# 01_fpga.net
KiCad netlist of a schematic drawn in Altium Designer
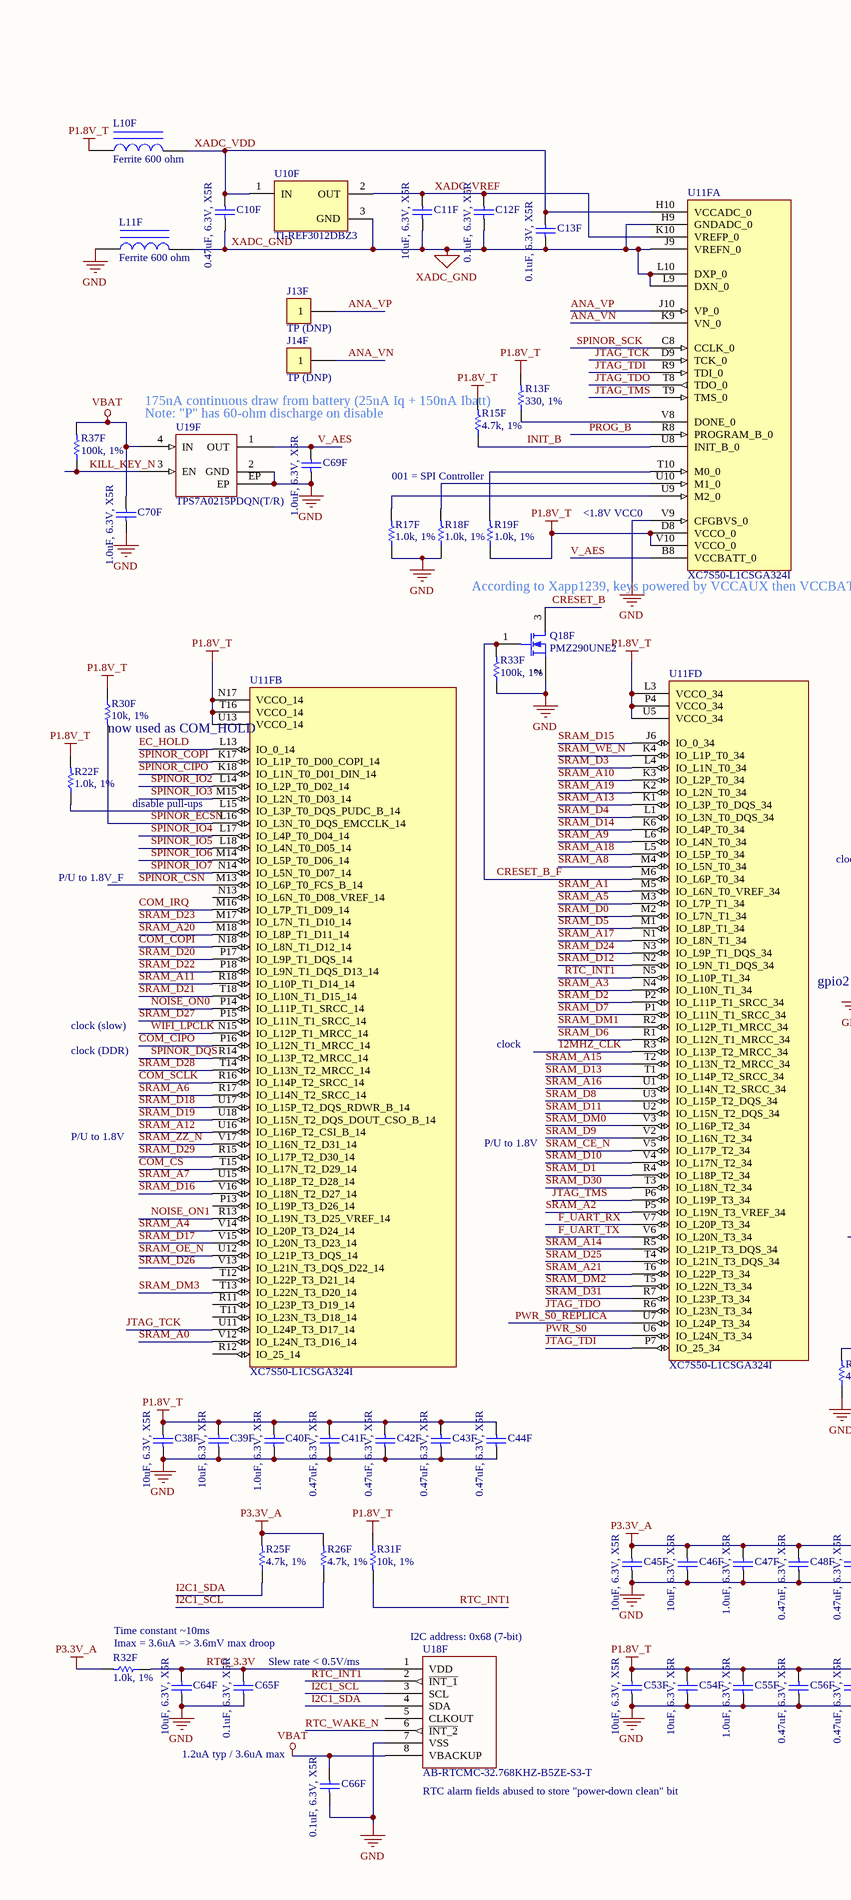
[diagram p0: 01_fpga.SchDoc, left]
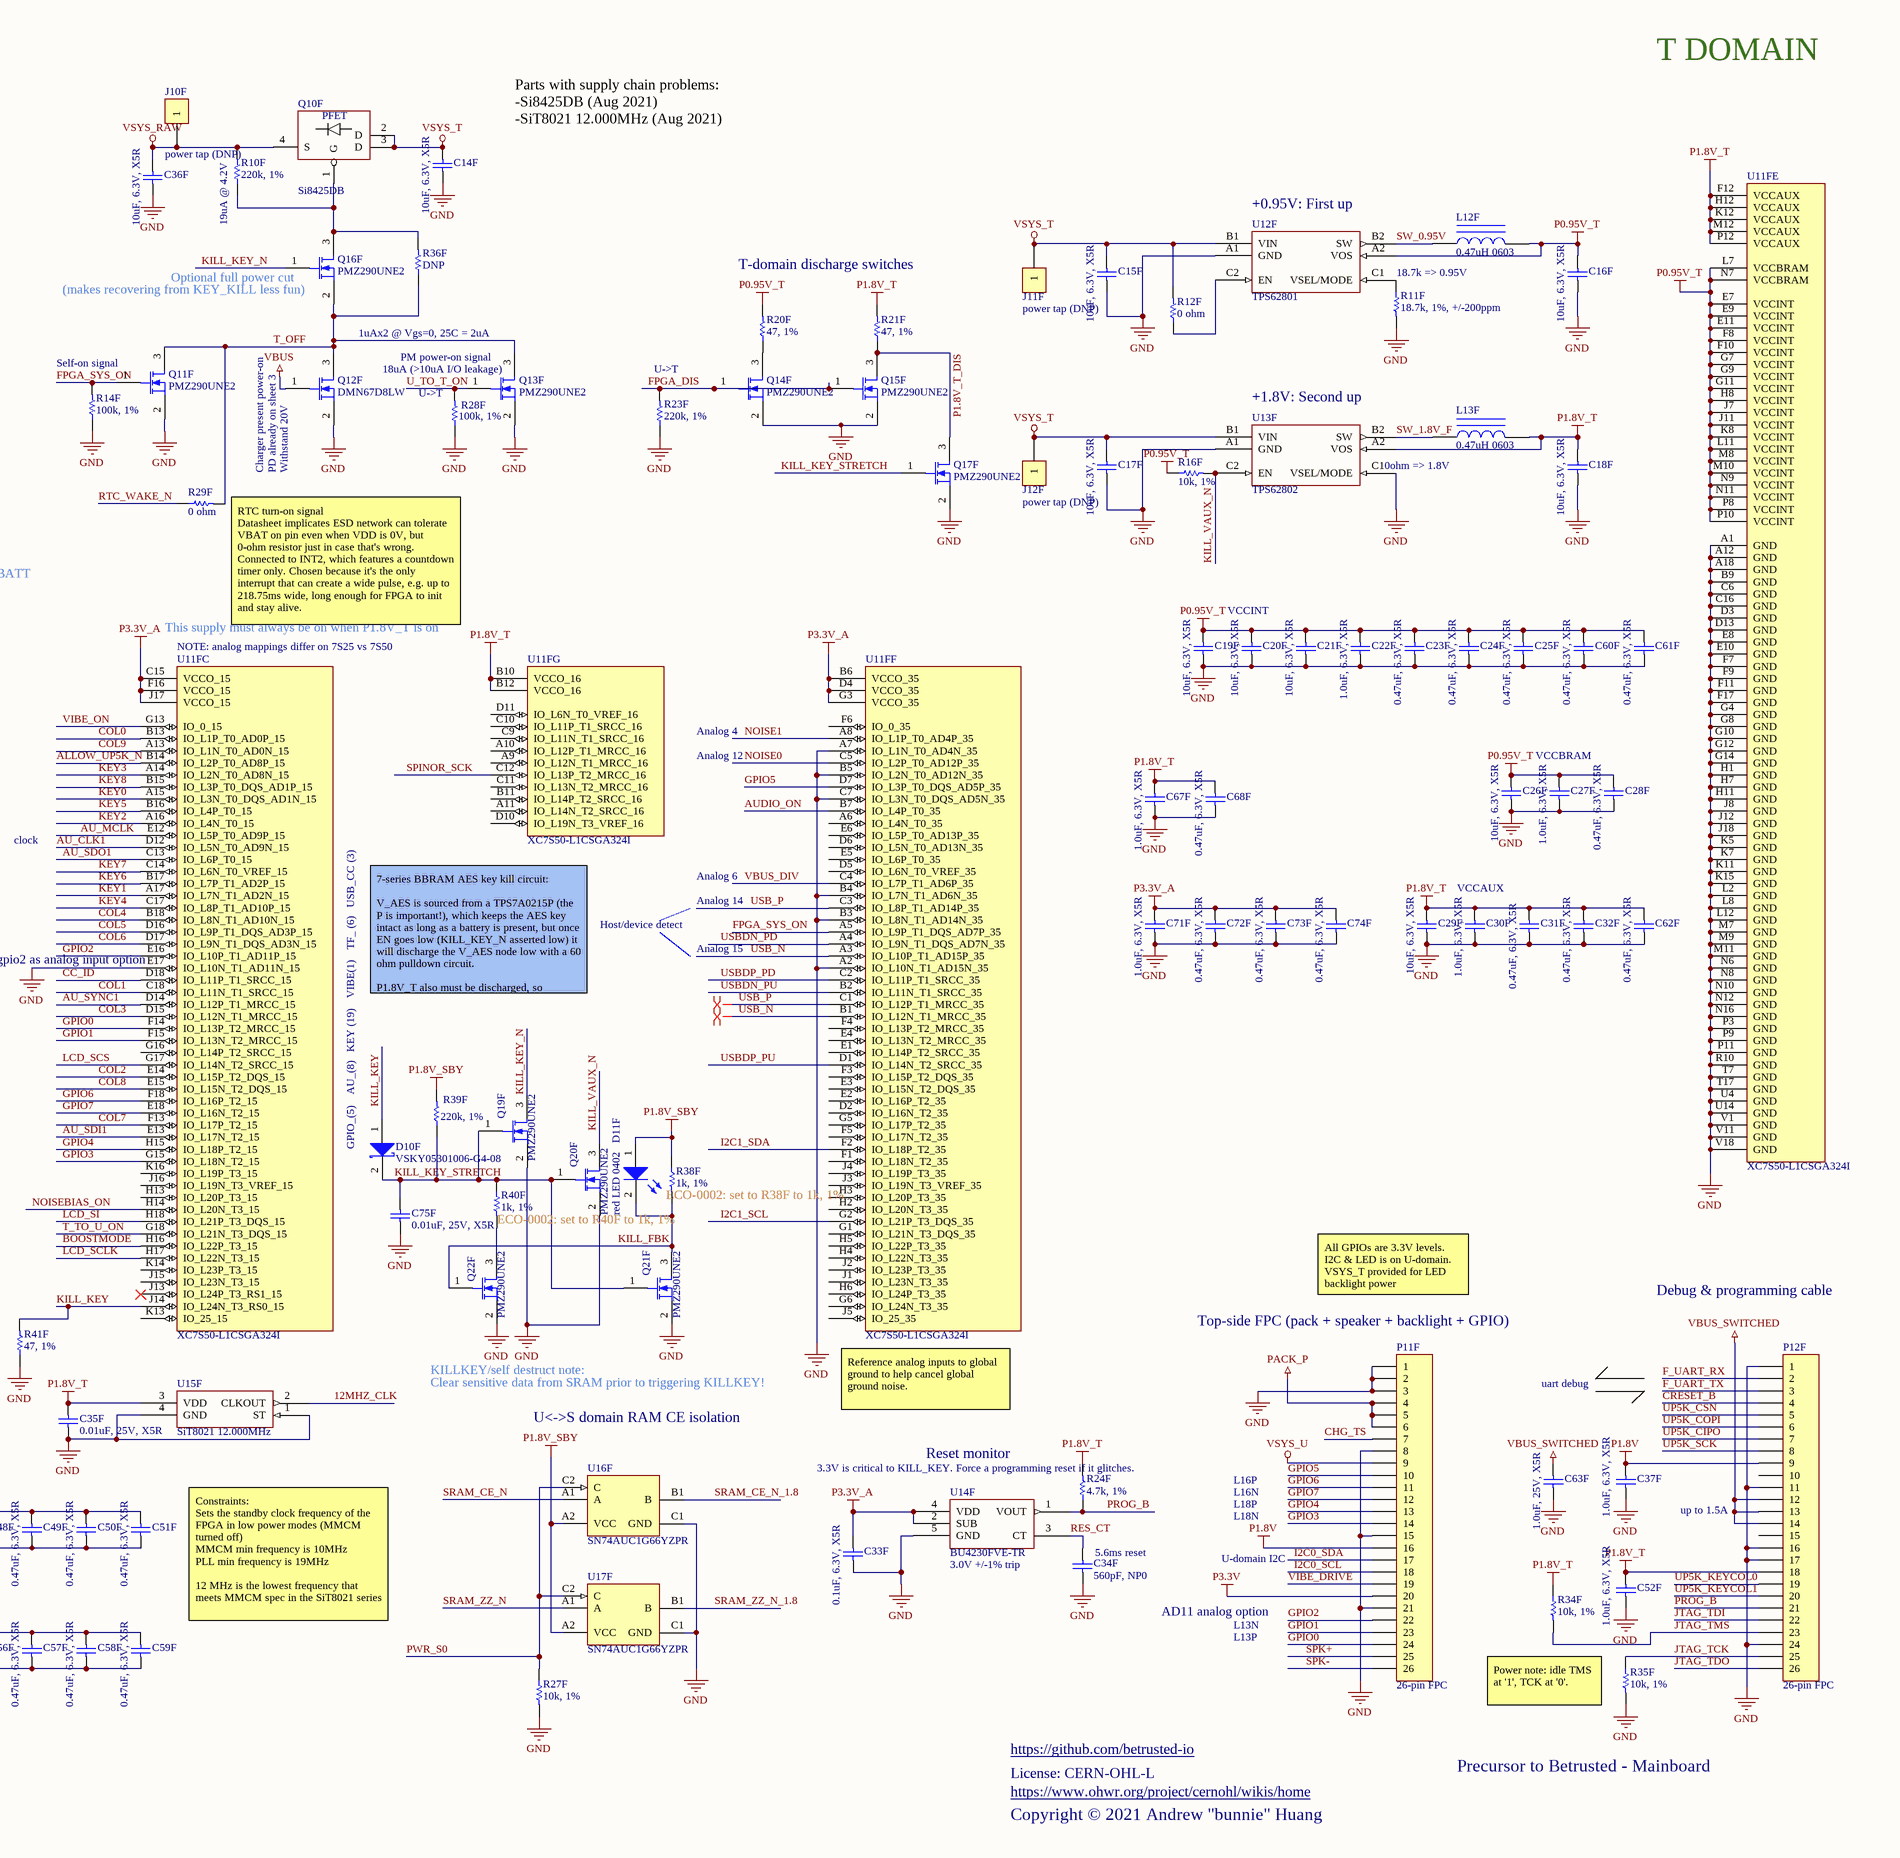
[diagram p1: 01_fpga.SchDoc, right]

(export (version "E")
  (design (tool "Eeschema 10.0.6"))
  (components
    (comp (ref "C10F")
      (value "0.47uF, 6.3V, X5R")
      (footprint "B_CAP0201")
      (description "Capacitor (Semiconductor SIM Model)")
      (fields (field (name "MPN") "CL03A474KQ3NNNH"))
      (libsource (lib "Miscellaneous Devices") (part "Cap Semi"))
    )
    (comp (ref "C11F")
      (value "10uF, 6.3V, X5R")
      (footprint "B_CAP0603")
      (description "Capacitor (Semiconductor SIM Model)")
      (fields (field (name "MPN") "CL10A106MQ8NNNC"))
      (libsource (lib "Miscellaneous Devices") (part "Cap Semi"))
    )
    (comp (ref "C12F")
      (value "0.1uF, 6.3V, X5R")
      (footprint "B_CAP0201")
      (description "Capacitor (Semiconductor SIM Model)")
      (fields (field (name "MPN") "CL03A104KQ3NNNC"))
      (libsource (lib "Miscellaneous Devices") (part "Cap Semi"))
    )
    (comp (ref "C13F")
      (value "0.1uF, 6.3V, X5R")
      (footprint "B_CAP0201")
      (description "Capacitor (Semiconductor SIM Model)")
      (fields (field (name "MPN") "CL03A104KQ3NNNC"))
      (libsource (lib "Miscellaneous Devices") (part "Cap Semi"))
    )
    (comp (ref "C14F")
      (value "10uF, 6.3V, X5R")
      (footprint "B_CAP0603")
      (description "Capacitor (Semiconductor SIM Model)")
      (fields (field (name "MPN") "CL10A106MQ8NNNC"))
      (libsource (lib "Miscellaneous Devices") (part "Cap Semi"))
    )
    (comp (ref "C15F")
      (value "10uF, 6.3V, X5R")
      (footprint "B_CAP0603")
      (description "Capacitor (Semiconductor SIM Model)")
      (fields (field (name "MPN") "CL10A106MQ8NNNC"))
      (libsource (lib "Miscellaneous Devices") (part "Cap Semi"))
    )
    (comp (ref "C16F")
      (value "10uF, 6.3V, X5R")
      (footprint "B_CAP0603")
      (description "Capacitor (Semiconductor SIM Model)")
      (fields (field (name "MPN") "CL10A106MQ8NNNC"))
      (libsource (lib "Miscellaneous Devices") (part "Cap Semi"))
    )
    (comp (ref "C17F")
      (value "10uF, 6.3V, X5R")
      (footprint "B_CAP0603")
      (description "Capacitor (Semiconductor SIM Model)")
      (fields (field (name "MPN") "CL10A106MQ8NNNC"))
      (libsource (lib "Miscellaneous Devices") (part "Cap Semi"))
    )
    (comp (ref "C18F")
      (value "10uF, 6.3V, X5R")
      (footprint "B_CAP0603")
      (description "Capacitor (Semiconductor SIM Model)")
      (fields (field (name "MPN") "CL10A106MQ8NNNC"))
      (libsource (lib "Miscellaneous Devices") (part "Cap Semi"))
    )
    (comp (ref "C19F")
      (value "10uF, 6.3V, X5R")
      (footprint "B_CAP0603")
      (description "Capacitor (Semiconductor SIM Model)")
      (fields (field (name "MPN") "CL10A106MQ8NNNC"))
      (libsource (lib "Miscellaneous Devices") (part "Cap Semi"))
    )
    (comp (ref "C20F")
      (value "10uF, 6.3V, X5R")
      (footprint "B_CAP0603")
      (description "Capacitor (Semiconductor SIM Model)")
      (fields (field (name "MPN") "CL10A106MQ8NNNC"))
      (libsource (lib "Miscellaneous Devices") (part "Cap Semi"))
    )
    (comp (ref "C21F")
      (value "10uF, 6.3V, X5R")
      (footprint "B_CAP0603")
      (description "Capacitor (Semiconductor SIM Model)")
      (fields (field (name "MPN") "CL10A106MQ8NNNC"))
      (libsource (lib "Miscellaneous Devices") (part "Cap Semi"))
    )
    (comp (ref "C22F")
      (value "1.0uF, 6.3V, X5R")
      (footprint "B_CAP0201")
      (description "Capacitor (Semiconductor SIM Model)")
      (fields (field (name "MPN") "GRM033R60J105MEA2D"))
      (libsource (lib "Miscellaneous Devices") (part "Cap Semi"))
    )
    (comp (ref "C23F")
      (value "0.47uF, 6.3V, X5R")
      (footprint "B_CAP0201")
      (description "Capacitor (Semiconductor SIM Model)")
      (fields (field (name "MPN") "CL03A474KQ3NNNH"))
      (libsource (lib "Miscellaneous Devices") (part "Cap Semi"))
    )
    (comp (ref "C24F")
      (value "0.47uF, 6.3V, X5R")
      (footprint "B_CAP0201")
      (description "Capacitor (Semiconductor SIM Model)")
      (fields (field (name "MPN") "CL03A474KQ3NNNH"))
      (libsource (lib "Miscellaneous Devices") (part "Cap Semi"))
    )
    (comp (ref "C25F")
      (value "0.47uF, 6.3V, X5R")
      (footprint "B_CAP0201")
      (description "Capacitor (Semiconductor SIM Model)")
      (fields (field (name "MPN") "CL03A474KQ3NNNH"))
      (libsource (lib "Miscellaneous Devices") (part "Cap Semi"))
    )
    (comp (ref "C26F")
      (value "10uF, 6.3V, X5R")
      (footprint "B_CAP0603")
      (description "Capacitor (Semiconductor SIM Model)")
      (fields (field (name "MPN") "CL10A106MQ8NNNC"))
      (libsource (lib "Miscellaneous Devices") (part "Cap Semi"))
    )
    (comp (ref "C27F")
      (value "1.0uF, 6.3V, X5R")
      (footprint "B_CAP0201")
      (description "Capacitor (Semiconductor SIM Model)")
      (fields (field (name "MPN") "GRM033R60J105MEA2D"))
      (libsource (lib "Miscellaneous Devices") (part "Cap Semi"))
    )
    (comp (ref "C28F")
      (value "0.47uF, 6.3V, X5R")
      (footprint "B_CAP0201")
      (description "Capacitor (Semiconductor SIM Model)")
      (fields (field (name "MPN") "CL03A474KQ3NNNH"))
      (libsource (lib "Miscellaneous Devices") (part "Cap Semi"))
    )
    (comp (ref "C29F")
      (value "10uF, 6.3V, X5R")
      (footprint "B_CAP0603")
      (description "Capacitor (Semiconductor SIM Model)")
      (fields (field (name "MPN") "CL10A106MQ8NNNC"))
      (libsource (lib "Miscellaneous Devices") (part "Cap Semi"))
    )
    (comp (ref "C30F")
      (value "1.0uF, 6.3V, X5R")
      (footprint "B_CAP0201")
      (description "Capacitor (Semiconductor SIM Model)")
      (fields (field (name "MPN") "GRM033R60J105MEA2D"))
      (libsource (lib "Miscellaneous Devices") (part "Cap Semi"))
    )
    (comp (ref "C31F")
      (value "0.47uF, 6.3V, X5R")
      (footprint "B_CAP0201")
      (description "Capacitor (Semiconductor SIM Model)")
      (fields (field (name "MPN") "CL03A474KQ3NNNH"))
      (libsource (lib "Miscellaneous Devices") (part "Cap Semi"))
    )
    (comp (ref "C32F")
      (value "0.47uF, 6.3V, X5R")
      (footprint "B_CAP0201")
      (description "Capacitor (Semiconductor SIM Model)")
      (fields (field (name "MPN") "CL03A474KQ3NNNH"))
      (libsource (lib "Miscellaneous Devices") (part "Cap Semi"))
    )
    (comp (ref "C33F")
      (value "0.1uF, 6.3V, X5R")
      (footprint "B_CAP0201")
      (description "Capacitor (Semiconductor SIM Model)")
      (fields (field (name "MPN") "CL03A104KQ3NNNC"))
      (libsource (lib "Miscellaneous Devices") (part "Cap Semi"))
    )
    (comp (ref "C34F")
      (value "560pF, NP0")
      (footprint "B_RES0201")
      (description "Capacitor (Semiconductor SIM Model)")
      (fields (field (name "MPN") "GRM0335C1E561JA01D"))
      (libsource (lib "Miscellaneous Devices") (part "Cap Semi"))
    )
    (comp (ref "C35F")
      (value "0.01uF, 25V, X5R")
      (footprint "B_RES0201")
      (description "Capacitor (Semiconductor SIM Model)")
      (fields (field (name "MPN") "GRM033R61E103KA12D"))
      (libsource (lib "Miscellaneous Devices") (part "Cap Semi"))
    )
    (comp (ref "C36F")
      (value "10uF, 6.3V, X5R")
      (footprint "B_CAP0603")
      (description "Capacitor (Semiconductor SIM Model)")
      (fields (field (name "MPN") "CL10A106MQ8NNNC"))
      (libsource (lib "Miscellaneous Devices") (part "Cap Semi"))
    )
    (comp (ref "C37F")
      (value "1.0uF, 6.3V, X5R")
      (footprint "B_CAP0201")
      (description "Capacitor (Semiconductor SIM Model)")
      (fields (field (name "MPN") "GRM033R60J105MEA2D"))
      (libsource (lib "Miscellaneous Devices") (part "Cap Semi"))
    )
    (comp (ref "C38F")
      (value "10uF, 6.3V, X5R")
      (footprint "B_CAP0603")
      (description "Capacitor (Semiconductor SIM Model)")
      (fields (field (name "MPN") "CL10A106MQ8NNNC"))
      (libsource (lib "Miscellaneous Devices") (part "Cap Semi"))
    )
    (comp (ref "C39F")
      (value "10uF, 6.3V, X5R")
      (footprint "B_CAP0603")
      (description "Capacitor (Semiconductor SIM Model)")
      (fields (field (name "MPN") "CL10A106MQ8NNNC"))
      (libsource (lib "Miscellaneous Devices") (part "Cap Semi"))
    )
    (comp (ref "C40F")
      (value "1.0uF, 6.3V, X5R")
      (footprint "B_CAP0201")
      (description "Capacitor (Semiconductor SIM Model)")
      (fields (field (name "MPN") "GRM033R60J105MEA2D"))
      (libsource (lib "Miscellaneous Devices") (part "Cap Semi"))
    )
    (comp (ref "C41F")
      (value "0.47uF, 6.3V, X5R")
      (footprint "B_CAP0201")
      (description "Capacitor (Semiconductor SIM Model)")
      (fields (field (name "MPN") "CL03A474KQ3NNNH"))
      (libsource (lib "Miscellaneous Devices") (part "Cap Semi"))
    )
    (comp (ref "C42F")
      (value "0.47uF, 6.3V, X5R")
      (footprint "B_CAP0201")
      (description "Capacitor (Semiconductor SIM Model)")
      (fields (field (name "MPN") "CL03A474KQ3NNNH"))
      (libsource (lib "Miscellaneous Devices") (part "Cap Semi"))
    )
    (comp (ref "C43F")
      (value "0.47uF, 6.3V, X5R")
      (footprint "B_CAP0201")
      (description "Capacitor (Semiconductor SIM Model)")
      (fields (field (name "MPN") "CL03A474KQ3NNNH"))
      (libsource (lib "Miscellaneous Devices") (part "Cap Semi"))
    )
    (comp (ref "C44F")
      (value "0.47uF, 6.3V, X5R")
      (footprint "B_CAP0201")
      (description "Capacitor (Semiconductor SIM Model)")
      (fields (field (name "MPN") "CL03A474KQ3NNNH"))
      (libsource (lib "Miscellaneous Devices") (part "Cap Semi"))
    )
    (comp (ref "C45F")
      (value "10uF, 6.3V, X5R")
      (footprint "B_CAP0603")
      (description "Capacitor (Semiconductor SIM Model)")
      (fields (field (name "MPN") "CL10A106MQ8NNNC"))
      (libsource (lib "Miscellaneous Devices") (part "Cap Semi"))
    )
    (comp (ref "C46F")
      (value "10uF, 6.3V, X5R")
      (footprint "B_CAP0603")
      (description "Capacitor (Semiconductor SIM Model)")
      (fields (field (name "MPN") "CL10A106MQ8NNNC"))
      (libsource (lib "Miscellaneous Devices") (part "Cap Semi"))
    )
    (comp (ref "C47F")
      (value "1.0uF, 6.3V, X5R")
      (footprint "B_CAP0201")
      (description "Capacitor (Semiconductor SIM Model)")
      (fields (field (name "MPN") "GRM033R60J105MEA2D"))
      (libsource (lib "Miscellaneous Devices") (part "Cap Semi"))
    )
    (comp (ref "C48F")
      (value "0.47uF, 6.3V, X5R")
      (footprint "B_CAP0201")
      (description "Capacitor (Semiconductor SIM Model)")
      (fields (field (name "MPN") "CL03A474KQ3NNNH"))
      (libsource (lib "Miscellaneous Devices") (part "Cap Semi"))
    )
    (comp (ref "C49F")
      (value "0.47uF, 6.3V, X5R")
      (footprint "B_CAP0201")
      (description "Capacitor (Semiconductor SIM Model)")
      (fields (field (name "MPN") "CL03A474KQ3NNNH"))
      (libsource (lib "Miscellaneous Devices") (part "Cap Semi"))
    )
    (comp (ref "C50F")
      (value "0.47uF, 6.3V, X5R")
      (footprint "B_CAP0201")
      (description "Capacitor (Semiconductor SIM Model)")
      (fields (field (name "MPN") "CL03A474KQ3NNNH"))
      (libsource (lib "Miscellaneous Devices") (part "Cap Semi"))
    )
    (comp (ref "C51F")
      (value "0.47uF, 6.3V, X5R")
      (footprint "B_CAP0201")
      (description "Capacitor (Semiconductor SIM Model)")
      (fields (field (name "MPN") "CL03A474KQ3NNNH"))
      (libsource (lib "Miscellaneous Devices") (part "Cap Semi"))
    )
    (comp (ref "C52F")
      (value "1.0uF, 6.3V, X5R")
      (footprint "B_CAP0201")
      (description "Capacitor (Semiconductor SIM Model)")
      (fields (field (name "MPN") "GRM033R60J105MEA2D"))
      (libsource (lib "Miscellaneous Devices") (part "Cap Semi"))
    )
    (comp (ref "C53F")
      (value "10uF, 6.3V, X5R")
      (footprint "B_CAP0603")
      (description "Capacitor (Semiconductor SIM Model)")
      (fields (field (name "MPN") "CL10A106MQ8NNNC"))
      (libsource (lib "Miscellaneous Devices") (part "Cap Semi"))
    )
    (comp (ref "C54F")
      (value "10uF, 6.3V, X5R")
      (footprint "B_CAP0603")
      (description "Capacitor (Semiconductor SIM Model)")
      (fields (field (name "MPN") "CL10A106MQ8NNNC"))
      (libsource (lib "Miscellaneous Devices") (part "Cap Semi"))
    )
    (comp (ref "C55F")
      (value "1.0uF, 6.3V, X5R")
      (footprint "B_CAP0201")
      (description "Capacitor (Semiconductor SIM Model)")
      (fields (field (name "MPN") "GRM033R60J105MEA2D"))
      (libsource (lib "Miscellaneous Devices") (part "Cap Semi"))
    )
    (comp (ref "C56F")
      (value "0.47uF, 6.3V, X5R")
      (footprint "B_CAP0201")
      (description "Capacitor (Semiconductor SIM Model)")
      (fields (field (name "MPN") "CL03A474KQ3NNNH"))
      (libsource (lib "Miscellaneous Devices") (part "Cap Semi"))
    )
    (comp (ref "C57F")
      (value "0.47uF, 6.3V, X5R")
      (footprint "B_CAP0201")
      (description "Capacitor (Semiconductor SIM Model)")
      (fields (field (name "MPN") "CL03A474KQ3NNNH"))
      (libsource (lib "Miscellaneous Devices") (part "Cap Semi"))
    )
    (comp (ref "C58F")
      (value "0.47uF, 6.3V, X5R")
      (footprint "B_CAP0201")
      (description "Capacitor (Semiconductor SIM Model)")
      (fields (field (name "MPN") "CL03A474KQ3NNNH"))
      (libsource (lib "Miscellaneous Devices") (part "Cap Semi"))
    )
    (comp (ref "C59F")
      (value "0.47uF, 6.3V, X5R")
      (footprint "B_CAP0201")
      (description "Capacitor (Semiconductor SIM Model)")
      (fields (field (name "MPN") "CL03A474KQ3NNNH"))
      (libsource (lib "Miscellaneous Devices") (part "Cap Semi"))
    )
    (comp (ref "C60F")
      (value "0.47uF, 6.3V, X5R")
      (footprint "B_CAP0201")
      (description "Capacitor (Semiconductor SIM Model)")
      (fields (field (name "MPN") "CL03A474KQ3NNNH"))
      (libsource (lib "Miscellaneous Devices") (part "Cap Semi"))
    )
    (comp (ref "C61F")
      (value "0.47uF, 6.3V, X5R")
      (footprint "B_CAP0201")
      (description "Capacitor (Semiconductor SIM Model)")
      (fields (field (name "MPN") "CL03A474KQ3NNNH"))
      (libsource (lib "Miscellaneous Devices") (part "Cap Semi"))
    )
    (comp (ref "C62F")
      (value "0.47uF, 6.3V, X5R")
      (footprint "B_CAP0201")
      (description "Capacitor (Semiconductor SIM Model)")
      (fields (field (name "MPN") "CL03A474KQ3NNNH"))
      (libsource (lib "Miscellaneous Devices") (part "Cap Semi"))
    )
    (comp (ref "C63F")
      (value "1.0uF, 25V, X5R")
      (footprint "B_CAP0603")
      (description "Capacitor (Semiconductor SIM Model)")
      (fields (field (name "MPN") "CL10A105KA8NNNC"))
      (libsource (lib "Miscellaneous Devices") (part "Cap Semi"))
    )
    (comp (ref "C64F")
      (value "10uF, 6.3V, X5R")
      (footprint "B_CAP0603")
      (description "Capacitor (Semiconductor SIM Model)")
      (fields (field (name "MPN") "CL10A106MQ8NNNC"))
      (libsource (lib "Miscellaneous Devices") (part "Cap Semi"))
    )
    (comp (ref "C65F")
      (value "0.1uF, 6.3V, X5R")
      (footprint "B_CAP0201")
      (description "Capacitor (Semiconductor SIM Model)")
      (fields (field (name "MPN") "CL03A104KQ3NNNC"))
      (libsource (lib "Miscellaneous Devices") (part "Cap Semi"))
    )
    (comp (ref "C66F")
      (value "0.1uF, 6.3V, X5R")
      (footprint "B_CAP0201")
      (description "Capacitor (Semiconductor SIM Model)")
      (fields (field (name "MPN") "CL03A104KQ3NNNC"))
      (libsource (lib "Miscellaneous Devices") (part "Cap Semi"))
    )
    (comp (ref "C67F")
      (value "1.0uF, 6.3V, X5R")
      (footprint "B_CAP0201")
      (description "Capacitor (Semiconductor SIM Model)")
      (fields (field (name "MPN") "GRM033R60J105MEA2D"))
      (libsource (lib "Miscellaneous Devices") (part "Cap Semi"))
    )
    (comp (ref "C68F")
      (value "0.47uF, 6.3V, X5R")
      (footprint "B_CAP0201")
      (description "Capacitor (Semiconductor SIM Model)")
      (fields (field (name "MPN") "CL03A474KQ3NNNH"))
      (libsource (lib "Miscellaneous Devices") (part "Cap Semi"))
    )
    (comp (ref "C69F")
      (value "1.0uF, 6.3V, X5R")
      (footprint "B_CAP0201")
      (description "Capacitor (Semiconductor SIM Model)")
      (fields (field (name "MPN") "GRM033R60J105MEA2D"))
      (libsource (lib "Miscellaneous Devices") (part "Cap Semi"))
    )
    (comp (ref "C70F")
      (value "1.0uF, 6.3V, X5R")
      (footprint "B_CAP0201")
      (description "Capacitor (Semiconductor SIM Model)")
      (fields (field (name "MPN") "GRM033R60J105MEA2D"))
      (libsource (lib "Miscellaneous Devices") (part "Cap Semi"))
    )
    (comp (ref "C71F")
      (value "1.0uF, 6.3V, X5R")
      (footprint "B_CAP0201")
      (description "Capacitor (Semiconductor SIM Model)")
      (fields (field (name "MPN") "GRM033R60J105MEA2D"))
      (libsource (lib "Miscellaneous Devices") (part "Cap Semi"))
    )
    (comp (ref "C72F")
      (value "0.47uF, 6.3V, X5R")
      (footprint "B_CAP0201")
      (description "Capacitor (Semiconductor SIM Model)")
      (fields (field (name "MPN") "CL03A474KQ3NNNH"))
      (libsource (lib "Miscellaneous Devices") (part "Cap Semi"))
    )
    (comp (ref "C73F")
      (value "0.47uF, 6.3V, X5R")
      (footprint "B_CAP0201")
      (description "Capacitor (Semiconductor SIM Model)")
      (fields (field (name "MPN") "CL03A474KQ3NNNH"))
      (libsource (lib "Miscellaneous Devices") (part "Cap Semi"))
    )
    (comp (ref "C74F")
      (value "0.47uF, 6.3V, X5R")
      (footprint "B_CAP0201")
      (description "Capacitor (Semiconductor SIM Model)")
      (fields (field (name "MPN") "CL03A474KQ3NNNH"))
      (libsource (lib "Miscellaneous Devices") (part "Cap Semi"))
    )
    (comp (ref "C75F")
      (value "0.01uF, 25V, X5R")
      (footprint "B_RES0201")
      (description "Capacitor (Semiconductor SIM Model)")
      (fields (field (name "MPN") "GRM033R61E103KA12D"))
      (libsource (lib "Miscellaneous Devices") (part "Cap Semi"))
    )
    (comp (ref "D10F")
      (value "VSKY05301006-G4-08")
      (footprint "B_DIO0402")
      (description "Schottky Rectifier")
      (libsource (lib "Miscellaneous Devices") (part "Diode 11DQ03"))
    )
    (comp (ref "D11F")
      (value "red LED 0402")
      (footprint "B_LED0402")
      (description "Red LED")
      (fields (field (name "MPN") "SML-P11UTT86R") (field (name "PUBLISHER") "Altium Limited"))
      (libsource (lib "Miscellaneous Devices") (part "LED2"))
    )
    (comp (ref "J10F")
      (value "power tap (DNP)")
      (footprint "RESTAP-0603")
      (description "Connector")
      (fields (field (name "MPN") "DNP"))
      (libsource (lib "") (part "CON1_2"))
    )
    (comp (ref "J11F")
      (value "power tap (DNP)")
      (footprint "B_PWRTAP0402")
      (description "Connector")
      (fields (field (name "MPN") "DNP"))
      (libsource (lib "*") (part "CON1"))
    )
    (comp (ref "J12F")
      (value "power tap (DNP)")
      (footprint "RESTAP-0603")
      (description "Connector")
      (fields (field (name "MPN") "DNP"))
      (libsource (lib "*") (part "CON1"))
    )
    (comp (ref "J13F")
      (value "TP (DNP)")
      (footprint "TP_0.4x0.4_SMT")
      (description "Connector")
      (fields (field (name "MPN") "DNP"))
      (libsource (lib "") (part "CON1_1"))
    )
    (comp (ref "J14F")
      (value "TP (DNP)")
      (footprint "TP_0.4x0.4_SMT")
      (description "Connector")
      (fields (field (name "MPN") "DNP"))
      (libsource (lib "") (part "CON1_1"))
    )
    (comp (ref "L10F")
      (value "Ferrite 600 ohm")
      (footprint "B_IND0603")
      (description "Magnetic-Core Inductor")
      (fields (field (name "MPN") "BLM18AG601SN1D"))
      (libsource (lib "Miscellaneous Devices") (part "Inductor Iron"))
    )
    (comp (ref "L11F")
      (value "Ferrite 600 ohm")
      (footprint "B_IND0603")
      (description "Magnetic-Core Inductor")
      (fields (field (name "MPN") "BLM18AG601SN1D"))
      (libsource (lib "Miscellaneous Devices") (part "Inductor Iron"))
    )
    (comp (ref "L12F")
      (value "0.47uH 0603")
      (footprint "B_IND0603")
      (description "Magnetic-Core Inductor")
      (fields (field (name "MPN") "TFM160808ALC-R47MTAA"))
      (libsource (lib "Miscellaneous Devices") (part "Inductor Iron"))
    )
    (comp (ref "L13F")
      (value "0.47uH 0603")
      (footprint "B_IND0603")
      (description "Magnetic-Core Inductor")
      (fields (field (name "MPN") "TFM160808ALC-R47MTAA"))
      (libsource (lib "Miscellaneous Devices") (part "Inductor Iron"))
    )
    (comp (ref "P11F")
      (value "26-pin FPC")
      (footprint "HRS_FH34SRJ-26S-0.5SH(50)")
      (description "26 Pin FPC header")
      (fields (field (name "MPN") "FH34SRJ-26S-0.5SH(99)"))
      (libsource (lib "commonsch-new") (part "FPC-26"))
    )
    (comp (ref "P12F")
      (value "26-pin FPC")
      (footprint "HRS_FH34SRJ-26S-0.5SH(50)")
      (description "26 Pin FPC header")
      (fields (field (name "MPN") "FH34SRJ-26S-0.5SH(99)"))
      (libsource (lib "commonsch-new") (part "FPC-26"))
    )
    (comp (ref "Q10F")
      (value "Si8425DB")
      (footprint "VISHAY_MICRO_FOOT_4_BUMP")
      (description "P-channel 20V 6.2A 27mOhm @ -2.5V")
      (fields (field (name "MPN") "SI8425DB-T1-E1"))
      (libsource (lib "temp-to-merge") (part "Si8425DB"))
    )
    (comp (ref "Q11F")
      (value "PMZ290UNE2")
      (footprint "SOT883")
      (description "N-Channel MOSFET")
      (fields (field (name "PUBLISHER") "Altium Limited"))
      (libsource (lib "Miscellaneous Devices") (part "MOSFET-N"))
    )
    (comp (ref "Q12F")
      (value "DMN67D8LW")
      (footprint "SOT323-3AN")
      (description "N-Channel MOSFET")
      (fields (field (name "PUBLISHER") "Altium Limited"))
      (libsource (lib "Miscellaneous Devices") (part "MOSFET-N"))
    )
    (comp (ref "Q13F")
      (value "PMZ290UNE2")
      (footprint "SOT883")
      (description "N-Channel MOSFET")
      (fields (field (name "PUBLISHER") "Altium Limited"))
      (libsource (lib "Miscellaneous Devices") (part "MOSFET-N"))
    )
    (comp (ref "Q14F")
      (value "PMZ290UNE2")
      (footprint "SOT883")
      (description "N-Channel MOSFET")
      (fields (field (name "PUBLISHER") "Altium Limited"))
      (libsource (lib "Miscellaneous Devices") (part "MOSFET-N"))
    )
    (comp (ref "Q15F")
      (value "PMZ290UNE2")
      (footprint "SOT883")
      (description "N-Channel MOSFET")
      (fields (field (name "PUBLISHER") "Altium Limited"))
      (libsource (lib "Miscellaneous Devices") (part "MOSFET-N"))
    )
    (comp (ref "Q16F")
      (value "PMZ290UNE2")
      (footprint "SOT883")
      (description "N-Channel MOSFET")
      (fields (field (name "PUBLISHER") "Altium Limited"))
      (libsource (lib "Miscellaneous Devices") (part "MOSFET-N"))
    )
    (comp (ref "Q17F")
      (value "PMZ290UNE2")
      (footprint "SOT883")
      (description "N-Channel MOSFET")
      (fields (field (name "PUBLISHER") "Altium Limited"))
      (libsource (lib "Miscellaneous Devices") (part "MOSFET-N"))
    )
    (comp (ref "Q18F")
      (value "PMZ290UNE2")
      (footprint "SOT883")
      (description "N-Channel MOSFET")
      (fields (field (name "PUBLISHER") "Altium Limited"))
      (libsource (lib "Miscellaneous Devices") (part "MOSFET-N"))
    )
    (comp (ref "Q19F")
      (value "PMZ290UNE2")
      (footprint "SOT883")
      (description "N-Channel MOSFET")
      (fields (field (name "PUBLISHER") "Altium Limited"))
      (libsource (lib "Miscellaneous Devices") (part "MOSFET-N"))
    )
    (comp (ref "Q20F")
      (value "PMZ290UNE2")
      (footprint "SOT883")
      (description "N-Channel MOSFET")
      (fields (field (name "PUBLISHER") "Altium Limited"))
      (libsource (lib "Miscellaneous Devices") (part "MOSFET-N"))
    )
    (comp (ref "Q21F")
      (value "PMZ290UNE2")
      (footprint "SOT883")
      (description "N-Channel MOSFET")
      (fields (field (name "PUBLISHER") "Altium Limited"))
      (libsource (lib "Miscellaneous Devices") (part "MOSFET-N"))
    )
    (comp (ref "Q22F")
      (value "PMZ290UNE2")
      (footprint "SOT883")
      (description "N-Channel MOSFET")
      (fields (field (name "PUBLISHER") "Altium Limited"))
      (libsource (lib "Miscellaneous Devices") (part "MOSFET-N"))
    )
    (comp (ref "R10F")
      (value "220k, 1%")
      (footprint "B_RES0201")
      (description "Resistor")
      (fields (field (name "MPN") "ANY"))
      (libsource (lib "Miscellaneous Devices") (part "Res1"))
    )
    (comp (ref "R11F")
      (value "18.7k, 1%, +/-200ppm")
      (footprint "B_RES0402")
      (description "Resistor")
      (fields (field (name "MPN") "RC0402FR-0718K7L"))
      (libsource (lib "Miscellaneous Devices") (part "Res1"))
    )
    (comp (ref "R12F")
      (value "0 ohm")
      (footprint "B_RES0201")
      (description "Resistor")
      (fields (field (name "MPN") "ANY"))
      (libsource (lib "Miscellaneous Devices") (part "Res1"))
    )
    (comp (ref "R13F")
      (value "330, 1%")
      (footprint "B_RES0201")
      (description "Resistor")
      (fields (field (name "MPN") "ANY"))
      (libsource (lib "Miscellaneous Devices") (part "Res1"))
    )
    (comp (ref "R14F")
      (value "100k, 1%")
      (footprint "B_RES0201")
      (description "Resistor")
      (fields (field (name "MPN") "ANY"))
      (libsource (lib "Miscellaneous Devices") (part "Res1"))
    )
    (comp (ref "R15F")
      (value "4.7k, 1%")
      (footprint "B_RES0201")
      (description "Resistor")
      (fields (field (name "MPN") "ANY"))
      (libsource (lib "Miscellaneous Devices") (part "Res1"))
    )
    (comp (ref "R16F")
      (value "10k, 1%")
      (footprint "B_RES0201")
      (description "Resistor")
      (fields (field (name "MPN") "ANY"))
      (libsource (lib "Miscellaneous Devices") (part "Res1"))
    )
    (comp (ref "R17F")
      (value "1.0k, 1%")
      (footprint "B_RES0201")
      (description "Resistor")
      (fields (field (name "MPN") "ANY"))
      (libsource (lib "Miscellaneous Devices") (part "Res1"))
    )
    (comp (ref "R18F")
      (value "1.0k, 1%")
      (footprint "B_RES0201")
      (description "Resistor")
      (fields (field (name "MPN") "ANY"))
      (libsource (lib "Miscellaneous Devices") (part "Res1"))
    )
    (comp (ref "R19F")
      (value "1.0k, 1%")
      (footprint "B_RES0201")
      (description "Resistor")
      (fields (field (name "MPN") "ANY"))
      (libsource (lib "Miscellaneous Devices") (part "Res1"))
    )
    (comp (ref "R20F")
      (value "47, 1%")
      (footprint "B_RES0402")
      (description "Resistor")
      (fields (field (name "MPN") "ANY"))
      (libsource (lib "Miscellaneous Devices") (part "Res1"))
    )
    (comp (ref "R21F")
      (value "47, 1%")
      (footprint "B_RES0402")
      (description "Resistor")
      (fields (field (name "MPN") "ANY"))
      (libsource (lib "Miscellaneous Devices") (part "Res1"))
    )
    (comp (ref "R22F")
      (value "1.0k, 1%")
      (footprint "B_RES0201")
      (description "Resistor")
      (fields (field (name "MPN") "ANY"))
      (libsource (lib "Miscellaneous Devices") (part "Res1"))
    )
    (comp (ref "R23F")
      (value "220k, 1%")
      (footprint "B_RES0201")
      (description "Resistor")
      (fields (field (name "MPN") "ANY"))
      (libsource (lib "Miscellaneous Devices") (part "Res1"))
    )
    (comp (ref "R24F")
      (value "4.7k, 1%")
      (footprint "B_RES0201")
      (description "Resistor")
      (fields (field (name "MPN") "ANY"))
      (libsource (lib "Miscellaneous Devices") (part "Res1"))
    )
    (comp (ref "R25F")
      (value "4.7k, 1%")
      (footprint "B_RES0201")
      (description "Resistor")
      (fields (field (name "MPN") "ANY"))
      (libsource (lib "Miscellaneous Devices") (part "Res1"))
    )
    (comp (ref "R26F")
      (value "4.7k, 1%")
      (footprint "B_RES0201")
      (description "Resistor")
      (fields (field (name "MPN") "ANY"))
      (libsource (lib "Miscellaneous Devices") (part "Res1"))
    )
    (comp (ref "R27F")
      (value "10k, 1%")
      (footprint "B_RES0201")
      (description "Resistor")
      (fields (field (name "MPN") "ANY"))
      (libsource (lib "Miscellaneous Devices") (part "Res1"))
    )
    (comp (ref "R28F")
      (value "100k, 1%")
      (footprint "B_RES0201")
      (description "Resistor")
      (fields (field (name "MPN") "ANY"))
      (libsource (lib "Miscellaneous Devices") (part "Res1"))
    )
    (comp (ref "R29F")
      (value "0 ohm")
      (footprint "B_RES0201")
      (description "Resistor")
      (fields (field (name "MPN") "ANY"))
      (libsource (lib "Miscellaneous Devices") (part "Res1"))
    )
    (comp (ref "R30F")
      (value "10k, 1%")
      (footprint "B_RES0201")
      (description "Resistor")
      (fields (field (name "MPN") "ANY"))
      (libsource (lib "Miscellaneous Devices") (part "Res1"))
    )
    (comp (ref "R31F")
      (value "10k, 1%")
      (footprint "B_RES0201")
      (description "Resistor")
      (fields (field (name "MPN") "ANY"))
      (libsource (lib "Miscellaneous Devices") (part "Res1"))
    )
    (comp (ref "R32F")
      (value "1.0k, 1%")
      (footprint "B_RES0201")
      (description "Resistor")
      (fields (field (name "MPN") "ANY"))
      (libsource (lib "Miscellaneous Devices") (part "Res1"))
    )
    (comp (ref "R33F")
      (value "100k, 1%")
      (footprint "B_RES0201")
      (description "Resistor")
      (fields (field (name "MPN") "ANY"))
      (libsource (lib "Miscellaneous Devices") (part "Res1"))
    )
    (comp (ref "R34F")
      (value "10k, 1%")
      (footprint "B_RES0201")
      (description "Resistor")
      (fields (field (name "MPN") "ANY"))
      (libsource (lib "Miscellaneous Devices") (part "Res1"))
    )
    (comp (ref "R35F")
      (value "10k, 1%")
      (footprint "B_RES0201")
      (description "Resistor")
      (fields (field (name "MPN") "ANY"))
      (libsource (lib "Miscellaneous Devices") (part "Res1"))
    )
    (comp (ref "R36F")
      (value "DNP")
      (footprint "B_RES0201")
      (description "Resistor")
      (fields (field (name "MPN") "ANY"))
      (libsource (lib "Miscellaneous Devices") (part "Res1"))
    )
    (comp (ref "R37F")
      (value "100k, 1%")
      (footprint "B_RES0201")
      (description "Resistor")
      (fields (field (name "MPN") "ANY"))
      (libsource (lib "Miscellaneous Devices") (part "Res1"))
    )
    (comp (ref "R38F")
      (value "1k, 1%")
      (footprint "B_RES0201")
      (description "Resistor")
      (fields (field (name "MPN") "ANY"))
      (libsource (lib "Miscellaneous Devices") (part "Res1"))
    )
    (comp (ref "R39F")
      (value "220k, 1%")
      (footprint "B_RES0201")
      (description "Resistor")
      (fields (field (name "MPN") "ANY"))
      (libsource (lib "Miscellaneous Devices") (part "Res1"))
    )
    (comp (ref "R40F")
      (value "1k, 1%")
      (footprint "B_RES0201")
      (description "Resistor")
      (fields (field (name "MPN") "ANY"))
      (libsource (lib "Miscellaneous Devices") (part "Res1"))
    )
    (comp (ref "R41F")
      (value "47, 1%")
      (footprint "B_RES0402")
      (description "Resistor")
      (fields (field (name "MPN") "ANY"))
      (libsource (lib "Miscellaneous Devices") (part "Res1"))
    )
    (comp (ref "U10F")
      (value "TI-REF3012DBZ3")
      (footprint "ONSC-SOT-23-3-318-08_V")
      (fields (field (name "MPN") "REF3012AIDBZT"))
      (libsource (lib "TI-REF3012DBZ3") (part "TI-REF3012DBZ3"))
    )
    (comp (ref "U11F")
      (value "XC7S50-L1CSGA324I")
      (footprint "BGA324C80P18X18_1500X1500X150")
      (description "Spartan 7 FPGA in CSGA324 package")
      (libsource (lib "commonsch-new") (part "XC7S50CSGA324"))
    )
    (comp (ref "U12F")
      (value "TPS62801")
      (footprint "BGA6C35P2X3_70X105X40_NSMD")
      (description "Buck regulator, 4MHz, 0.6A, 0.8V-1.55V, low Iq")
      (fields (field (name "MPN") "TPS62801YKAT"))
      (libsource (lib "altium-import") (part "root_0_TPS62801_"))
    )
    (comp (ref "U13F")
      (value "TPS62802")
      (footprint "BGA6C35P2X3_70X105X40_NSMD")
      (description "Buck regulator, 4MHz, 0.6A, 1.8V-3.3V, low Iq")
      (fields (field (name "MPN") "TPS62802YKAR"))
      (libsource (lib "altium-import") (part "root_0_TPS62802_"))
    )
    (comp (ref "U14F")
      (value "BU4230FVE-TR")
      (footprint "ROHM_VSOF5")
      (description "Low voltage free delay time setting CMOS voltage detector IC")
      (libsource (lib "commonsch-new") (part "BU42xxFVE"))
    )
    (comp (ref "U15F")
      (value "SiT8021 12.000MHz")
      (footprint "SiTIME_CSP")
      (description "1 to 26 MHz micropower oscillator")
      (fields (field (name "MPN") "SIT8021AI-J4-18S-12.000000E"))
      (libsource (lib "altium-import") (part "root_2_SiT8021_"))
    )
    (comp (ref "U16F")
      (value "SN74AUC1G66YZPR")
      (footprint "YZP0005ADAD")
      (description "Single Bilateral Analog Switch, YZP0005ADAD, LARGE T&R")
      (fields
        (field (name "MANUFACTURER") "Texas Instruments")
        (field (name "GENERIC PART NUMBER") "SN74AUC1G66")
      )
      (libsource (lib "Components - 04.06.19 - 14.52") (part "CMP-0859-01029-3"))
    )
    (comp (ref "U17F")
      (value "SN74AUC1G66YZPR")
      (footprint "YZP0005ADAD")
      (description "Single Bilateral Analog Switch, YZP0005ADAD, LARGE T&R")
      (fields
        (field (name "MANUFACTURER") "Texas Instruments")
        (field (name "GENERIC PART NUMBER") "SN74AUC1G66")
      )
      (libsource (lib "Components - 04.06.19 - 14.52") (part "CMP-0859-01029-3"))
    )
    (comp (ref "U18F")
      (value "AB-RTCMC-32.768KHZ-B5ZE-S3-T")
      (footprint "ABRACON_RTCMC_LGA10")
      (description "RTC Module with I2C Bus")
      (libsource (lib "commonsch-new") (part "AB-RTCMC-32.768kHZ-B5ZE-S3"))
    )
    (comp (ref "U19F")
      (value "TPS7A0215PDQN(T/R)")
      (footprint "TI_DQN_X2SON")
      (description "Nanopower Iq, 25-nA, 200mA LDO with fast transient response")
      (libsource (lib "commonsch-new") (part "TPS7A02xxPDQN"))
    )
  )
  (nets
    (net (code "1") (name "/12MHZ_CLK") (class "Default")
      (node (ref "U11F") (pin "R3") (pinfunction "IO_L13P_T2_MRCC_34_R3") (pintype "bidirectional"))
      (node (ref "U15F") (pin "2") (pinfunction "CLKOUT_2") (pintype "output"))
    )
    (net (code "2") (name "/ALLOW_UP5K_N") (class "Default")
      (node (ref "U11F") (pin "B14") (pinfunction "IO_L2P_T0_AD8P_15_B14") (pintype "bidirectional"))
    )
    (net (code "3") (name "/ANA_VN") (class "Default")
      (node (ref "J14F") (pin "1") (pinfunction "1_1") (pintype "passive"))
      (node (ref "U11F") (pin "K9") (pinfunction "VN_0_K9") (pintype "passive"))
    )
    (net (code "4") (name "/ANA_VP") (class "Default")
      (node (ref "J13F") (pin "1") (pinfunction "1_1") (pintype "passive"))
      (node (ref "U11F") (pin "J10") (pinfunction "VP_0_J10") (pintype "input"))
    )
    (net (code "5") (name "/AUDIO_ON") (class "Default")
      (node (ref "U11F") (pin "B7") (pinfunction "IO_L4P_T0_35_B7") (pintype "bidirectional"))
    )
    (net (code "6") (name "/AU_CLK1") (class "Default")
      (node (ref "U11F") (pin "D12") (pinfunction "IO_L5N_T0_AD9N_15_D12") (pintype "bidirectional"))
    )
    (net (code "7") (name "/AU_MCLK") (class "Default")
      (node (ref "U11F") (pin "E12") (pinfunction "IO_L5P_T0_AD9P_15_E12") (pintype "bidirectional"))
    )
    (net (code "8") (name "/AU_SDI1") (class "Default")
      (node (ref "U11F") (pin "E13") (pinfunction "IO_L17N_T2_15_E13") (pintype "bidirectional"))
    )
    (net (code "9") (name "/AU_SDO1") (class "Default")
      (node (ref "U11F") (pin "C13") (pinfunction "IO_L6P_T0_15_C13") (pintype "bidirectional"))
    )
    (net (code "10") (name "/AU_SYNC1") (class "Default")
      (node (ref "U11F") (pin "D14") (pinfunction "IO_L12P_T1_MRCC_15_D14") (pintype "bidirectional"))
    )
    (net (code "11") (name "/BOOSTMODE") (class "Default")
      (node (ref "U11F") (pin "H16") (pinfunction "IO_L22P_T3_15_H16") (pintype "bidirectional"))
    )
    (net (code "12") (name "/CC_ID") (class "Default")
      (node (ref "U11F") (pin "D18") (pinfunction "IO_L11P_T1_SRCC_15_D18") (pintype "bidirectional"))
    )
    (net (code "13") (name "/CHG_TS") (class "Default")
      (node (ref "P11F") (pin "7") (pinfunction "7_7") (pintype "passive"))
    )
    (net (code "14") (name "/COL0") (class "Default")
      (node (ref "U11F") (pin "B13") (pinfunction "IO_L1P_T0_AD0P_15_B13") (pintype "bidirectional"))
    )
    (net (code "15") (name "/COL1") (class "Default")
      (node (ref "U11F") (pin "C18") (pinfunction "IO_L11N_T1_SRCC_15_C18") (pintype "bidirectional"))
    )
    (net (code "16") (name "/COL2") (class "Default")
      (node (ref "U11F") (pin "E14") (pinfunction "IO_L15P_T2_DQS_15_E14") (pintype "bidirectional"))
    )
    (net (code "17") (name "/COL3") (class "Default")
      (node (ref "U11F") (pin "D15") (pinfunction "IO_L12N_T1_MRCC_15_D15") (pintype "bidirectional"))
    )
    (net (code "18") (name "/COL4") (class "Default")
      (node (ref "U11F") (pin "B18") (pinfunction "IO_L8N_T1_AD10N_15_B18") (pintype "bidirectional"))
    )
    (net (code "19") (name "/COL5") (class "Default")
      (node (ref "U11F") (pin "D16") (pinfunction "IO_L9P_T1_DQS_AD3P_15_D16") (pintype "bidirectional"))
    )
    (net (code "20") (name "/COL6") (class "Default")
      (node (ref "U11F") (pin "D17") (pinfunction "IO_L9N_T1_DQS_AD3N_15_D17") (pintype "bidirectional"))
    )
    (net (code "21") (name "/COL7") (class "Default")
      (node (ref "U11F") (pin "F13") (pinfunction "IO_L17P_T2_15_F13") (pintype "bidirectional"))
    )
    (net (code "22") (name "/COL8") (class "Default")
      (node (ref "U11F") (pin "E15") (pinfunction "IO_L15N_T2_DQS_15_E15") (pintype "bidirectional"))
    )
    (net (code "23") (name "/COL9") (class "Default")
      (node (ref "U11F") (pin "A13") (pinfunction "IO_L1N_T0_AD0N_15_A13") (pintype "bidirectional"))
    )
    (net (code "24") (name "/COM_CIPO") (class "Default")
      (node (ref "U11F") (pin "P16") (pinfunction "IO_L12N_T1_MRCC_14_P16") (pintype "bidirectional"))
    )
    (net (code "25") (name "/COM_COPI") (class "Default")
      (node (ref "U11F") (pin "N18") (pinfunction "IO_L8N_T1_D12_14_N18") (pintype "bidirectional"))
    )
    (net (code "26") (name "/COM_CS") (class "Default")
      (node (ref "U11F") (pin "T15") (pinfunction "IO_L17N_T2_D29_14_T15") (pintype "bidirectional"))
    )
    (net (code "27") (name "/COM_IRQ") (class "Default")
      (node (ref "U11F") (pin "M16") (pinfunction "IO_L7P_T1_D09_14_M16") (pintype "bidirectional"))
    )
    (net (code "28") (name "/COM_SCLK") (class "Default")
      (node (ref "U11F") (pin "R16") (pinfunction "IO_L14P_T2_SRCC_14_R16") (pintype "bidirectional"))
    )
    (net (code "29") (name "/CRESET_B") (class "Default")
      (node (ref "P12F") (pin "4") (pinfunction "4_4") (pintype "passive"))
      (node (ref "Q18F") (pin "3") (pinfunction "D_3") (pintype "passive"))
    )
    (net (code "30") (name "/CRESET_B_F") (class "Default")
      (node (ref "Q18F") (pin "1") (pinfunction "G_1") (pintype "passive"))
      (node (ref "R33F") (pin "2") (pinfunction "2_2") (pintype "passive"))
      (node (ref "U11F") (pin "M6") (pinfunction "IO_L6P_T0_34_M6") (pintype "bidirectional"))
    )
    (net (code "31") (name "/EC_HOLD") (class "Default")
      (node (ref "U11F") (pin "L13") (pinfunction "IO_0_14_L13") (pintype "bidirectional"))
    )
    (net (code "32") (name "/FPGA_DIS") (class "Default")
      (node (ref "Q14F") (pin "1") (pinfunction "G_1") (pintype "passive"))
      (node (ref "Q15F") (pin "1") (pinfunction "G_1") (pintype "passive"))
      (node (ref "R23F") (pin "2") (pinfunction "2_2") (pintype "passive"))
    )
    (net (code "33") (name "/FPGA_SYS_ON") (class "Default")
      (node (ref "Q11F") (pin "1") (pinfunction "G_1") (pintype "passive"))
      (node (ref "R14F") (pin "2") (pinfunction "2_2") (pintype "passive"))
      (node (ref "U11F") (pin "A5") (pinfunction "IO_L9P_T1_DQS_AD7P_35_A5") (pintype "bidirectional"))
    )
    (net (code "34") (name "/F_UART_RX") (class "Default")
      (node (ref "P12F") (pin "2") (pinfunction "2_2") (pintype "passive"))
      (node (ref "U11F") (pin "V7") (pinfunction "IO_L20P_T3_34_V7") (pintype "bidirectional"))
    )
    (net (code "35") (name "/F_UART_TX") (class "Default")
      (node (ref "P12F") (pin "3") (pinfunction "3_3") (pintype "passive"))
      (node (ref "U11F") (pin "V6") (pinfunction "IO_L20N_T3_34_V6") (pintype "bidirectional"))
    )
    (net (code "36") (name "/GPIO0") (class "Default")
      (node (ref "P11F") (pin "24") (pinfunction "24_24") (pintype "passive"))
      (node (ref "U11F") (pin "F14") (pinfunction "IO_L13P_T2_MRCC_15_F14") (pintype "bidirectional"))
    )
    (net (code "37") (name "/GPIO1") (class "Default")
      (node (ref "P11F") (pin "23") (pinfunction "23_23") (pintype "passive"))
      (node (ref "U11F") (pin "F15") (pinfunction "IO_L13N_T2_MRCC_15_F15") (pintype "bidirectional"))
    )
    (net (code "38") (name "/GPIO2") (class "Default")
      (node (ref "P11F") (pin "22") (pinfunction "22_22") (pintype "passive"))
      (node (ref "U11F") (pin "E16") (pinfunction "IO_L10P_T1_AD11P_15_E16") (pintype "bidirectional"))
    )
    (net (code "39") (name "/GPIO3") (class "Default")
      (node (ref "P11F") (pin "14") (pinfunction "14_14") (pintype "passive"))
      (node (ref "U11F") (pin "G15") (pinfunction "IO_L18N_T2_15_G15") (pintype "bidirectional"))
    )
    (net (code "40") (name "/GPIO4") (class "Default")
      (node (ref "P11F") (pin "13") (pinfunction "13_13") (pintype "passive"))
      (node (ref "U11F") (pin "H15") (pinfunction "IO_L18P_T2_15_H15") (pintype "bidirectional"))
    )
    (net (code "41") (name "/GPIO5") (class "Default")
      (node (ref "P11F") (pin "10") (pinfunction "10_10") (pintype "passive"))
      (node (ref "U11F") (pin "D7") (pinfunction "IO_L3P_T0_DQS_AD5P_35_D7") (pintype "bidirectional"))
    )
    (net (code "42") (name "/GPIO6") (class "Default")
      (node (ref "P11F") (pin "11") (pinfunction "11_11") (pintype "passive"))
      (node (ref "U11F") (pin "F18") (pinfunction "IO_L16P_T2_15_F18") (pintype "bidirectional"))
    )
    (net (code "43") (name "/GPIO7") (class "Default")
      (node (ref "P11F") (pin "12") (pinfunction "12_12") (pintype "passive"))
      (node (ref "U11F") (pin "E18") (pinfunction "IO_L16N_T2_15_E18") (pintype "bidirectional"))
    )
    (net (code "44") (name "/I2C0_SCL") (class "Default")
      (node (ref "P11F") (pin "18") (pinfunction "18_18") (pintype "passive"))
    )
    (net (code "45") (name "/I2C0_SDA") (class "Default")
      (node (ref "P11F") (pin "17") (pinfunction "17_17") (pintype "passive"))
    )
    (net (code "46") (name "/I2C1_SCL") (class "Default")
      (node (ref "R26F") (pin "1") (pinfunction "1_1") (pintype "passive"))
      (node (ref "U11F") (pin "G2") (pinfunction "IO_L21P_T3_DQS_35_G2") (pintype "bidirectional"))
      (node (ref "U18F") (pin "3") (pinfunction "SCL_3") (pintype "open_collector"))
    )
    (net (code "47") (name "/I2C1_SDA") (class "Default")
      (node (ref "R25F") (pin "1") (pinfunction "1_1") (pintype "passive"))
      (node (ref "U11F") (pin "F2") (pinfunction "IO_L18P_T2_35_F2") (pintype "bidirectional"))
      (node (ref "U18F") (pin "4") (pinfunction "SDA_4") (pintype "open_collector"))
    )
    (net (code "48") (name "/INIT_B") (class "Default")
      (node (ref "R15F") (pin "1") (pinfunction "1_1") (pintype "passive"))
      (node (ref "U11F") (pin "U8") (pinfunction "INIT_B_0_U8") (pintype "open_collector"))
    )
    (net (code "49") (name "/JTAG_TCK") (class "Default")
      (node (ref "P12F") (pin "25") (pinfunction "25_25") (pintype "passive"))
      (node (ref "R35F") (pin "1") (pinfunction "1_1") (pintype "passive"))
      (node (ref "U11F") (pin "D9") (pinfunction "TCK_0_D9") (pintype "input"))
      (node (ref "U11F") (pin "U11") (pinfunction "IO_L24P_T3_D17_14_U11") (pintype "bidirectional"))
    )
    (net (code "50") (name "/JTAG_TDI") (class "Default")
      (node (ref "P12F") (pin "22") (pinfunction "22_22") (pintype "passive"))
      (node (ref "U11F") (pin "P7") (pinfunction "IO_25_34_P7") (pintype "bidirectional"))
      (node (ref "U11F") (pin "R9") (pinfunction "TDI_0_R9") (pintype "input"))
    )
    (net (code "51") (name "/JTAG_TDO") (class "Default")
      (node (ref "P12F") (pin "26") (pinfunction "26_26") (pintype "passive"))
      (node (ref "U11F") (pin "R6") (pinfunction "IO_L23N_T3_34_R6") (pintype "bidirectional"))
      (node (ref "U11F") (pin "T8") (pinfunction "TDO_0_T8") (pintype "output"))
    )
    (net (code "52") (name "/JTAG_TMS") (class "Default")
      (node (ref "P12F") (pin "23") (pinfunction "23_23") (pintype "passive"))
      (node (ref "R34F") (pin "2") (pinfunction "2_2") (pintype "passive"))
      (node (ref "U11F") (pin "P6") (pinfunction "IO_L19P_T3_34_P6") (pintype "bidirectional"))
      (node (ref "U11F") (pin "T9") (pinfunction "TMS_0_T9") (pintype "input"))
    )
    (net (code "53") (name "/KEY0") (class "Default")
      (node (ref "U11F") (pin "A15") (pinfunction "IO_L3N_T0_DQS_AD1N_15_A15") (pintype "bidirectional"))
    )
    (net (code "54") (name "/KEY1") (class "Default")
      (node (ref "U11F") (pin "A17") (pinfunction "IO_L7N_T1_AD2N_15_A17") (pintype "bidirectional"))
    )
    (net (code "55") (name "/KEY2") (class "Default")
      (node (ref "U11F") (pin "A16") (pinfunction "IO_L4N_T0_15_A16") (pintype "bidirectional"))
    )
    (net (code "56") (name "/KEY3") (class "Default")
      (node (ref "U11F") (pin "A14") (pinfunction "IO_L2N_T0_AD8N_15_A14") (pintype "bidirectional"))
    )
    (net (code "57") (name "/KEY4") (class "Default")
      (node (ref "U11F") (pin "C17") (pinfunction "IO_L8P_T1_AD10P_15_C17") (pintype "bidirectional"))
    )
    (net (code "58") (name "/KEY5") (class "Default")
      (node (ref "U11F") (pin "B16") (pinfunction "IO_L4P_T0_15_B16") (pintype "bidirectional"))
    )
    (net (code "59") (name "/KEY6") (class "Default")
      (node (ref "U11F") (pin "B17") (pinfunction "IO_L7P_T1_AD2P_15_B17") (pintype "bidirectional"))
    )
    (net (code "60") (name "/KEY7") (class "Default")
      (node (ref "U11F") (pin "C14") (pinfunction "IO_L6N_T0_VREF_15_C14") (pintype "bidirectional"))
    )
    (net (code "61") (name "/KEY8") (class "Default")
      (node (ref "U11F") (pin "B15") (pinfunction "IO_L3P_T0_DQS_AD1P_15_B15") (pintype "bidirectional"))
    )
    (net (code "62") (name "/KILL_FBK") (class "Default")
      (node (ref "D11F") (pin "2") (pinfunction "K_2") (pintype "passive"))
      (node (ref "Q21F") (pin "3") (pinfunction "D_3") (pintype "passive"))
      (node (ref "Q22F") (pin "1") (pinfunction "G_1") (pintype "passive"))
      (node (ref "R38F") (pin "2") (pinfunction "2_2") (pintype "passive"))
    )
    (net (code "63") (name "/KILL_KEY") (class "Default")
      (node (ref "D10F") (pin "1") (pinfunction "A_1") (pintype "passive"))
      (node (ref "R41F") (pin "2") (pinfunction "2_2") (pintype "passive"))
      (node (ref "U11F") (pin "J14") (pinfunction "IO_L24N_T3_RS0_15_J14") (pintype "bidirectional"))
    )
    (net (code "64") (name "/KILL_KEY_N") (class "Default")
      (node (ref "Q16F") (pin "1") (pinfunction "G_1") (pintype "passive"))
      (node (ref "Q19F") (pin "3") (pinfunction "D_3") (pintype "passive"))
      (node (ref "R37F") (pin "1") (pinfunction "1_1") (pintype "passive"))
      (node (ref "U19F") (pin "3") (pinfunction "EN_3") (pintype "input"))
    )
    (net (code "65") (name "/KILL_KEY_STRETCH") (class "Default")
      (node (ref "C75F") (pin "1") (pinfunction "1_1") (pintype "passive"))
      (node (ref "D10F") (pin "2") (pinfunction "K_2") (pintype "passive"))
      (node (ref "Q17F") (pin "1") (pinfunction "G_1") (pintype "passive"))
      (node (ref "Q19F") (pin "1") (pinfunction "G_1") (pintype "passive"))
      (node (ref "Q20F") (pin "1") (pinfunction "G_1") (pintype "passive"))
      (node (ref "Q21F") (pin "1") (pinfunction "G_1") (pintype "passive"))
      (node (ref "R39F") (pin "1") (pinfunction "1_1") (pintype "passive"))
      (node (ref "R40F") (pin "1") (pinfunction "1_1") (pintype "passive"))
    )
    (net (code "66") (name "/KILL_VAUX_N") (class "Default")
      (node (ref "Q20F") (pin "3") (pinfunction "D_3") (pintype "passive"))
      (node (ref "R16F") (pin "2") (pinfunction "2_2") (pintype "passive"))
      (node (ref "U13F") (pin "C2") (pinfunction "EN_C2") (pintype "input"))
    )
    (net (code "67") (name "/LCD_SCLK") (class "Default")
      (node (ref "U11F") (pin "H17") (pinfunction "IO_L22N_T3_15_H17") (pintype "bidirectional"))
    )
    (net (code "68") (name "/LCD_SCS") (class "Default")
      (node (ref "U11F") (pin "G17") (pinfunction "IO_L14N_T2_SRCC_15_G17") (pintype "bidirectional"))
    )
    (net (code "69") (name "/LCD_SI") (class "Default")
      (node (ref "U11F") (pin "H18") (pinfunction "IO_L21P_T3_DQS_15_H18") (pintype "bidirectional"))
    )
    (net (code "70") (name "/NOISE0") (class "Default")
      (node (ref "U11F") (pin "C5") (pinfunction "IO_L2P_T0_AD12P_35_C5") (pintype "bidirectional"))
    )
    (net (code "71") (name "/NOISE1") (class "Default")
      (node (ref "U11F") (pin "A8") (pinfunction "IO_L1P_T0_AD4P_35_A8") (pintype "bidirectional"))
    )
    (net (code "72") (name "/NOISEBIAS_ON") (class "Default")
      (node (ref "U11F") (pin "H14") (pinfunction "IO_L20N_T3_15_H14") (pintype "bidirectional"))
    )
    (net (code "73") (name "/NOISE_ON0") (class "Default")
      (node (ref "U11F") (pin "P14") (pinfunction "IO_L11P_T1_SRCC_14_P14") (pintype "bidirectional"))
    )
    (net (code "74") (name "/NOISE_ON1") (class "Default")
      (node (ref "U11F") (pin "R13") (pinfunction "IO_L19N_T3_D25_VREF_14_R13") (pintype "bidirectional"))
    )
    (net (code "75") (name "/P1.8V_T_DIS") (class "Default")
      (node (ref "Q15F") (pin "3") (pinfunction "D_3") (pintype "passive"))
      (node (ref "Q17F") (pin "3") (pinfunction "D_3") (pintype "passive"))
      (node (ref "R21F") (pin "1") (pinfunction "1_1") (pintype "passive"))
    )
    (net (code "76") (name "/PROG_B") (class "Default")
      (node (ref "P12F") (pin "21") (pinfunction "21_21") (pintype "passive"))
      (node (ref "R24F") (pin "1") (pinfunction "1_1") (pintype "passive"))
      (node (ref "U11F") (pin "R8") (pinfunction "PROGRAM_B_0_R8") (pintype "input"))
      (node (ref "U14F") (pin "1") (pinfunction "VOUT_1") (pintype "output"))
    )
    (net (code "77") (name "/PWR_S0") (class "Default")
      (node (ref "R27F") (pin "1") (pinfunction "1_1") (pintype "passive"))
      (node (ref "U11F") (pin "U6") (pinfunction "IO_L24N_T3_34_U6") (pintype "bidirectional"))
      (node (ref "U16F") (pin "C2") (pinfunction "C_C2") (pintype "input"))
      (node (ref "U17F") (pin "C2") (pinfunction "C_C2") (pintype "input"))
    )
    (net (code "78") (name "/PWR_S0_REPLICA") (class "Default")
      (node (ref "U11F") (pin "U7") (pinfunction "IO_L24P_T3_34_U7") (pintype "bidirectional"))
    )
    (net (code "79") (name "/RES_CT") (class "Default")
      (node (ref "C34F") (pin "1") (pinfunction "1_1") (pintype "passive"))
      (node (ref "U14F") (pin "3") (pinfunction "CT_3") (pintype "passive"))
    )
    (net (code "80") (name "/RTC_3.3V") (class "Default")
      (node (ref "C64F") (pin "1") (pinfunction "1_1") (pintype "passive"))
      (node (ref "C65F") (pin "1") (pinfunction "1_1") (pintype "passive"))
      (node (ref "R32F") (pin "1") (pinfunction "1_1") (pintype "passive"))
      (node (ref "U18F") (pin "1") (pinfunction "VDD_1") (pintype "power_in"))
    )
    (net (code "81") (name "/RTC_INT1") (class "Default")
      (node (ref "R31F") (pin "2") (pinfunction "2_2") (pintype "passive"))
      (node (ref "U11F") (pin "N5") (pinfunction "IO_L10P_T1_34_N5") (pintype "bidirectional"))
      (node (ref "U18F") (pin "2") (pinfunction "~{INT_1}_2") (pintype "output"))
    )
    (net (code "82") (name "/RTC_WAKE_N") (class "Default")
      (node (ref "R29F") (pin "1") (pinfunction "1_1") (pintype "passive"))
      (node (ref "U18F") (pin "6") (pinfunction "~{INT_2}_6") (pintype "output"))
    )
    (net (code "83") (name "/SPINOR_CIPO") (class "Default")
      (node (ref "U11F") (pin "K18") (pinfunction "IO_L1N_T0_D01_DIN_14_K18") (pintype "bidirectional"))
    )
    (net (code "84") (name "/SPINOR_COPI") (class "Default")
      (node (ref "U11F") (pin "K17") (pinfunction "IO_L1P_T0_D00_MOSI_14_K17") (pintype "bidirectional"))
    )
    (net (code "85") (name "/SPINOR_CSN") (class "Default")
      (node (ref "U11F") (pin "M13") (pinfunction "IO_L6P_T0_FCS_B_14_M13") (pintype "bidirectional"))
    )
    (net (code "86") (name "/SPINOR_DQS") (class "Default")
      (node (ref "U11F") (pin "R14") (pinfunction "IO_L13P_T2_MRCC_14_R14") (pintype "bidirectional"))
    )
    (net (code "87") (name "/SPINOR_ECSN") (class "Default")
      (node (ref "R30F") (pin "2") (pinfunction "2_2") (pintype "passive"))
      (node (ref "U11F") (pin "L16") (pinfunction "IO_L3N_T0_DQS_EMCCLK_14_L16") (pintype "bidirectional"))
    )
    (net (code "88") (name "/SPINOR_IO2") (class "Default")
      (node (ref "U11F") (pin "L14") (pinfunction "IO_L2P_T0_D02_14_L14") (pintype "bidirectional"))
    )
    (net (code "89") (name "/SPINOR_IO3") (class "Default")
      (node (ref "U11F") (pin "M15") (pinfunction "IO_L2N_T0_D03_14_M15") (pintype "bidirectional"))
    )
    (net (code "90") (name "/SPINOR_IO4") (class "Default")
      (node (ref "U11F") (pin "L17") (pinfunction "IO_L4P_T0_D04_14_L17") (pintype "bidirectional"))
    )
    (net (code "91") (name "/SPINOR_IO5") (class "Default")
      (node (ref "U11F") (pin "L18") (pinfunction "IO_L4N_T0_D05_14_L18") (pintype "bidirectional"))
    )
    (net (code "92") (name "/SPINOR_IO6") (class "Default")
      (node (ref "U11F") (pin "M14") (pinfunction "IO_L5P_T0_D06_14_M14") (pintype "bidirectional"))
    )
    (net (code "93") (name "/SPINOR_IO7") (class "Default")
      (node (ref "U11F") (pin "N14") (pinfunction "IO_L5N_T0_D07_14_N14") (pintype "bidirectional"))
    )
    (net (code "94") (name "/SPINOR_SCK") (class "Default")
      (node (ref "U11F") (pin "C12") (pinfunction "IO_L13P_T2_MRCC_16_C12") (pintype "bidirectional"))
      (node (ref "U11F") (pin "C8") (pinfunction "CCLK_0_C8") (pintype "input"))
    )
    (net (code "95") (name "/SPK+") (class "Default")
      (node (ref "P11F") (pin "25") (pinfunction "25_25") (pintype "passive"))
    )
    (net (code "96") (name "/SPK-") (class "Default")
      (node (ref "P11F") (pin "26") (pinfunction "26_26") (pintype "passive"))
    )
    (net (code "97") (name "/SRAM_A0") (class "Default")
      (node (ref "U11F") (pin "V12") (pinfunction "IO_L24N_T3_D16_14_V12") (pintype "bidirectional"))
    )
    (net (code "98") (name "/SRAM_A1") (class "Default")
      (node (ref "U11F") (pin "M5") (pinfunction "IO_L6N_T0_VREF_34_M5") (pintype "bidirectional"))
    )
    (net (code "99") (name "/SRAM_A2") (class "Default")
      (node (ref "U11F") (pin "P5") (pinfunction "IO_L19N_T3_VREF_34_P5") (pintype "bidirectional"))
    )
    (net (code "100") (name "/SRAM_A3") (class "Default")
      (node (ref "U11F") (pin "N4") (pinfunction "IO_L10N_T1_34_N4") (pintype "bidirectional"))
    )
    (net (code "101") (name "/SRAM_A4") (class "Default")
      (node (ref "U11F") (pin "V14") (pinfunction "IO_L20P_T3_D24_14_V14") (pintype "bidirectional"))
    )
    (net (code "102") (name "/SRAM_A5") (class "Default")
      (node (ref "U11F") (pin "M3") (pinfunction "IO_L7P_T1_34_M3") (pintype "bidirectional"))
    )
    (net (code "103") (name "/SRAM_A6") (class "Default")
      (node (ref "U11F") (pin "R17") (pinfunction "IO_L14N_T2_SRCC_14_R17") (pintype "bidirectional"))
    )
    (net (code "104") (name "/SRAM_A7") (class "Default")
      (node (ref "U11F") (pin "U15") (pinfunction "IO_L18P_T2_D28_14_U15") (pintype "bidirectional"))
    )
    (net (code "105") (name "/SRAM_A8") (class "Default")
      (node (ref "U11F") (pin "M4") (pinfunction "IO_L5N_T0_34_M4") (pintype "bidirectional"))
    )
    (net (code "106") (name "/SRAM_A9") (class "Default")
      (node (ref "U11F") (pin "L6") (pinfunction "IO_L4N_T0_34_L6") (pintype "bidirectional"))
    )
    (net (code "107") (name "/SRAM_A10") (class "Default")
      (node (ref "U11F") (pin "K3") (pinfunction "IO_L2P_T0_34_K3") (pintype "bidirectional"))
    )
    (net (code "108") (name "/SRAM_A11") (class "Default")
      (node (ref "U11F") (pin "R18") (pinfunction "IO_L10P_T1_D14_14_R18") (pintype "bidirectional"))
    )
    (net (code "109") (name "/SRAM_A12") (class "Default")
      (node (ref "U11F") (pin "U16") (pinfunction "IO_L16P_T2_CSI_B_14_U16") (pintype "bidirectional"))
    )
    (net (code "110") (name "/SRAM_A13") (class "Default")
      (node (ref "U11F") (pin "K1") (pinfunction "IO_L3P_T0_DQS_34_K1") (pintype "bidirectional"))
    )
    (net (code "111") (name "/SRAM_A14") (class "Default")
      (node (ref "U11F") (pin "R5") (pinfunction "IO_L21P_T3_DQS_34_R5") (pintype "bidirectional"))
    )
    (net (code "112") (name "/SRAM_A15") (class "Default")
      (node (ref "U11F") (pin "T2") (pinfunction "IO_L13N_T2_MRCC_34_T2") (pintype "bidirectional"))
    )
    (net (code "113") (name "/SRAM_A16") (class "Default")
      (node (ref "U11F") (pin "U1") (pinfunction "IO_L14N_T2_SRCC_34_U1") (pintype "bidirectional"))
    )
    (net (code "114") (name "/SRAM_A17") (class "Default")
      (node (ref "U11F") (pin "N1") (pinfunction "IO_L8N_T1_34_N1") (pintype "bidirectional"))
    )
    (net (code "115") (name "/SRAM_A18") (class "Default")
      (node (ref "U11F") (pin "L5") (pinfunction "IO_L5P_T0_34_L5") (pintype "bidirectional"))
    )
    (net (code "116") (name "/SRAM_A19") (class "Default")
      (node (ref "U11F") (pin "K2") (pinfunction "IO_L2N_T0_34_K2") (pintype "bidirectional"))
    )
    (net (code "117") (name "/SRAM_A20") (class "Default")
      (node (ref "U11F") (pin "M18") (pinfunction "IO_L8P_T1_D11_14_M18") (pintype "bidirectional"))
    )
    (net (code "118") (name "/SRAM_A21") (class "Default")
      (node (ref "U11F") (pin "T6") (pinfunction "IO_L22P_T3_34_T6") (pintype "bidirectional"))
    )
    (net (code "119") (name "/SRAM_CE_N") (class "Default")
      (node (ref "U11F") (pin "V5") (pinfunction "IO_L17P_T2_34_V5") (pintype "bidirectional"))
      (node (ref "U16F") (pin "A1") (pinfunction "A_A1") (pintype "passive"))
    )
    (net (code "120") (name "/SRAM_CE_N_1.8") (class "Default")
      (node (ref "U16F") (pin "B1") (pinfunction "B_B1") (pintype "passive"))
    )
    (net (code "121") (name "/SRAM_D0") (class "Default")
      (node (ref "U11F") (pin "M2") (pinfunction "IO_L7N_T1_34_M2") (pintype "bidirectional"))
    )
    (net (code "122") (name "/SRAM_D1") (class "Default")
      (node (ref "U11F") (pin "R4") (pinfunction "IO_L18P_T2_34_R4") (pintype "bidirectional"))
    )
    (net (code "123") (name "/SRAM_D2") (class "Default")
      (node (ref "U11F") (pin "P2") (pinfunction "IO_L11P_T1_SRCC_34_P2") (pintype "bidirectional"))
    )
    (net (code "124") (name "/SRAM_D3") (class "Default")
      (node (ref "U11F") (pin "L4") (pinfunction "IO_L1N_T0_34_L4") (pintype "bidirectional"))
    )
    (net (code "125") (name "/SRAM_D4") (class "Default")
      (node (ref "U11F") (pin "L1") (pinfunction "IO_L3N_T0_DQS_34_L1") (pintype "bidirectional"))
    )
    (net (code "126") (name "/SRAM_D5") (class "Default")
      (node (ref "U11F") (pin "M1") (pinfunction "IO_L8P_T1_34_M1") (pintype "bidirectional"))
    )
    (net (code "127") (name "/SRAM_D6") (class "Default")
      (node (ref "U11F") (pin "R1") (pinfunction "IO_L12N_T1_MRCC_34_R1") (pintype "bidirectional"))
    )
    (net (code "128") (name "/SRAM_D7") (class "Default")
      (node (ref "U11F") (pin "P1") (pinfunction "IO_L11N_T1_SRCC_34_P1") (pintype "bidirectional"))
    )
    (net (code "129") (name "/SRAM_D8") (class "Default")
      (node (ref "U11F") (pin "U3") (pinfunction "IO_L15P_T2_DQS_34_U3") (pintype "bidirectional"))
    )
    (net (code "130") (name "/SRAM_D9") (class "Default")
      (node (ref "U11F") (pin "V2") (pinfunction "IO_L16N_T2_34_V2") (pintype "bidirectional"))
    )
    (net (code "131") (name "/SRAM_D10") (class "Default")
      (node (ref "U11F") (pin "V4") (pinfunction "IO_L17N_T2_34_V4") (pintype "bidirectional"))
    )
    (net (code "132") (name "/SRAM_D11") (class "Default")
      (node (ref "U11F") (pin "U2") (pinfunction "IO_L15N_T2_DQS_34_U2") (pintype "bidirectional"))
    )
    (net (code "133") (name "/SRAM_D12") (class "Default")
      (node (ref "U11F") (pin "N2") (pinfunction "IO_L9N_T1_DQS_34_N2") (pintype "bidirectional"))
    )
    (net (code "134") (name "/SRAM_D13") (class "Default")
      (node (ref "U11F") (pin "T1") (pinfunction "IO_L14P_T2_SRCC_34_T1") (pintype "bidirectional"))
    )
    (net (code "135") (name "/SRAM_D14") (class "Default")
      (node (ref "U11F") (pin "K6") (pinfunction "IO_L4P_T0_34_K6") (pintype "bidirectional"))
    )
    (net (code "136") (name "/SRAM_D15") (class "Default")
      (node (ref "U11F") (pin "J6") (pinfunction "IO_0_34_J6") (pintype "bidirectional"))
    )
    (net (code "137") (name "/SRAM_D16") (class "Default")
      (node (ref "U11F") (pin "V16") (pinfunction "IO_L18N_T2_D27_14_V16") (pintype "bidirectional"))
    )
    (net (code "138") (name "/SRAM_D17") (class "Default")
      (node (ref "U11F") (pin "V15") (pinfunction "IO_L20N_T3_D23_14_V15") (pintype "bidirectional"))
    )
    (net (code "139") (name "/SRAM_D18") (class "Default")
      (node (ref "U11F") (pin "U17") (pinfunction "IO_L15P_T2_DQS_RDWR_B_14_U17") (pintype "bidirectional"))
    )
    (net (code "140") (name "/SRAM_D19") (class "Default")
      (node (ref "U11F") (pin "U18") (pinfunction "IO_L15N_T2_DQS_DOUT_CSO_B_14_U18") (pintype "bidirectional"))
    )
    (net (code "141") (name "/SRAM_D20") (class "Default")
      (node (ref "U11F") (pin "P17") (pinfunction "IO_L9P_T1_DQS_14_P17") (pintype "bidirectional"))
    )
    (net (code "142") (name "/SRAM_D21") (class "Default")
      (node (ref "U11F") (pin "T18") (pinfunction "IO_L10N_T1_D15_14_T18") (pintype "bidirectional"))
    )
    (net (code "143") (name "/SRAM_D22") (class "Default")
      (node (ref "U11F") (pin "P18") (pinfunction "IO_L9N_T1_DQS_D13_14_P18") (pintype "bidirectional"))
    )
    (net (code "144") (name "/SRAM_D23") (class "Default")
      (node (ref "U11F") (pin "M17") (pinfunction "IO_L7N_T1_D10_14_M17") (pintype "bidirectional"))
    )
    (net (code "145") (name "/SRAM_D24") (class "Default")
      (node (ref "U11F") (pin "N3") (pinfunction "IO_L9P_T1_DQS_34_N3") (pintype "bidirectional"))
    )
    (net (code "146") (name "/SRAM_D25") (class "Default")
      (node (ref "U11F") (pin "T4") (pinfunction "IO_L21N_T3_DQS_34_T4") (pintype "bidirectional"))
    )
    (net (code "147") (name "/SRAM_D26") (class "Default")
      (node (ref "U11F") (pin "V13") (pinfunction "IO_L21N_T3_DQS_D22_14_V13") (pintype "bidirectional"))
    )
    (net (code "148") (name "/SRAM_D27") (class "Default")
      (node (ref "U11F") (pin "P15") (pinfunction "IO_L11N_T1_SRCC_14_P15") (pintype "bidirectional"))
    )
    (net (code "149") (name "/SRAM_D28") (class "Default")
      (node (ref "U11F") (pin "T14") (pinfunction "IO_L13N_T2_MRCC_14_T14") (pintype "bidirectional"))
    )
    (net (code "150") (name "/SRAM_D29") (class "Default")
      (node (ref "U11F") (pin "R15") (pinfunction "IO_L17P_T2_D30_14_R15") (pintype "bidirectional"))
    )
    (net (code "151") (name "/SRAM_D30") (class "Default")
      (node (ref "U11F") (pin "T3") (pinfunction "IO_L18N_T2_34_T3") (pintype "bidirectional"))
    )
    (net (code "152") (name "/SRAM_D31") (class "Default")
      (node (ref "U11F") (pin "R7") (pinfunction "IO_L23P_T3_34_R7") (pintype "bidirectional"))
    )
    (net (code "153") (name "/SRAM_DM0") (class "Default")
      (node (ref "U11F") (pin "V3") (pinfunction "IO_L16P_T2_34_V3") (pintype "bidirectional"))
    )
    (net (code "154") (name "/SRAM_DM1") (class "Default")
      (node (ref "U11F") (pin "R2") (pinfunction "IO_L12P_T1_MRCC_34_R2") (pintype "bidirectional"))
    )
    (net (code "155") (name "/SRAM_DM2") (class "Default")
      (node (ref "U11F") (pin "T5") (pinfunction "IO_L22N_T3_34_T5") (pintype "bidirectional"))
    )
    (net (code "156") (name "/SRAM_DM3") (class "Default")
      (node (ref "U11F") (pin "T13") (pinfunction "IO_L22N_T3_D20_14_T13") (pintype "bidirectional"))
    )
    (net (code "157") (name "/SRAM_OE_N") (class "Default")
      (node (ref "U11F") (pin "U12") (pinfunction "IO_L21P_T3_DQS_14_U12") (pintype "bidirectional"))
    )
    (net (code "158") (name "/SRAM_WE_N") (class "Default")
      (node (ref "U11F") (pin "K4") (pinfunction "IO_L1P_T0_34_K4") (pintype "bidirectional"))
    )
    (net (code "159") (name "/SRAM_ZZ_N") (class "Default")
      (node (ref "U11F") (pin "V17") (pinfunction "IO_L16N_T2_D31_14_V17") (pintype "bidirectional"))
      (node (ref "U17F") (pin "A1") (pinfunction "A_A1") (pintype "passive"))
    )
    (net (code "160") (name "/SRAM_ZZ_N_1.8") (class "Default")
      (node (ref "U17F") (pin "B1") (pinfunction "B_B1") (pintype "passive"))
    )
    (net (code "161") (name "/SW_0.95V") (class "Default")
      (node (ref "L12F") (pin "1") (pinfunction "1_1") (pintype "passive"))
      (node (ref "U12F") (pin "B2") (pinfunction "SW_B2") (pintype "output"))
    )
    (net (code "162") (name "/SW_1.8V_F") (class "Default")
      (node (ref "L13F") (pin "1") (pinfunction "1_1") (pintype "passive"))
      (node (ref "U13F") (pin "B2") (pinfunction "SW_B2") (pintype "output"))
    )
    (net (code "163") (name "/T_OFF") (class "Default")
      (node (ref "Q11F") (pin "3") (pinfunction "D_3") (pintype "passive"))
      (node (ref "Q12F") (pin "3") (pinfunction "D_3") (pintype "passive"))
      (node (ref "Q13F") (pin "3") (pinfunction "D_3") (pintype "passive"))
      (node (ref "Q16F") (pin "2") (pinfunction "S_2") (pintype "passive"))
      (node (ref "R29F") (pin "2") (pinfunction "2_2") (pintype "passive"))
      (node (ref "R36F") (pin "1") (pinfunction "1_1") (pintype "passive"))
    )
    (net (code "164") (name "/T_TO_U_ON") (class "Default")
      (node (ref "U11F") (pin "G18") (pinfunction "IO_L21N_T3_DQS_15_G18") (pintype "bidirectional"))
    )
    (net (code "165") (name "/UP5K_CIPO") (class "Default")
      (node (ref "P12F") (pin "7") (pinfunction "7_7") (pintype "passive"))
    )
    (net (code "166") (name "/UP5K_COPI") (class "Default")
      (node (ref "P12F") (pin "6") (pinfunction "6_6") (pintype "passive"))
    )
    (net (code "167") (name "/UP5K_CSN") (class "Default")
      (node (ref "P12F") (pin "5") (pinfunction "5_5") (pintype "passive"))
    )
    (net (code "168") (name "/UP5K_KEYCOL0") (class "Default")
      (node (ref "P12F") (pin "19") (pinfunction "19_19") (pintype "passive"))
    )
    (net (code "169") (name "/UP5K_KEYCOL1") (class "Default")
      (node (ref "P12F") (pin "20") (pinfunction "20_20") (pintype "passive"))
    )
    (net (code "170") (name "/UP5K_SCK") (class "Default")
      (node (ref "P12F") (pin "8") (pinfunction "8_8") (pintype "passive"))
    )
    (net (code "171") (name "/USBDN_PD") (class "Default")
      (node (ref "U11F") (pin "A4") (pinfunction "IO_L9N_T1_DQS_AD7N_35_A4") (pintype "bidirectional"))
    )
    (net (code "172") (name "/USBDN_PU") (class "Default")
      (node (ref "U11F") (pin "B2") (pinfunction "IO_L11N_T1_SRCC_35_B2") (pintype "bidirectional"))
    )
    (net (code "173") (name "/USBDP_PD") (class "Default")
      (node (ref "U11F") (pin "C2") (pinfunction "IO_L11P_T1_SRCC_35_C2") (pintype "bidirectional"))
    )
    (net (code "174") (name "/USBDP_PU") (class "Default")
      (node (ref "U11F") (pin "D1") (pinfunction "IO_L14N_T2_SRCC_35_D1") (pintype "bidirectional"))
    )
    (net (code "175") (name "/USB_N") (class "Default")
      (node (ref "U11F") (pin "A3") (pinfunction "IO_L10P_T1_AD15P_35_A3") (pintype "bidirectional"))
      (node (ref "U11F") (pin "B1") (pinfunction "IO_L12N_T1_MRCC_35_B1") (pintype "bidirectional"))
    )
    (net (code "176") (name "/USB_P") (class "Default")
      (node (ref "U11F") (pin "C1") (pinfunction "IO_L12P_T1_MRCC_35_C1") (pintype "bidirectional"))
      (node (ref "U11F") (pin "C3") (pinfunction "IO_L8P_T1_AD14P_35_C3") (pintype "bidirectional"))
    )
    (net (code "177") (name "/U_TO_T_ON") (class "Default")
      (node (ref "Q13F") (pin "1") (pinfunction "G_1") (pintype "passive"))
      (node (ref "R28F") (pin "2") (pinfunction "2_2") (pintype "passive"))
    )
    (net (code "178") (name "/VBUS_DIV") (class "Default")
      (node (ref "U11F") (pin "C4") (pinfunction "IO_L7P_T1_AD6P_35_C4") (pintype "bidirectional"))
    )
    (net (code "179") (name "/VIBE_DRIVE") (class "Default")
      (node (ref "P11F") (pin "19") (pinfunction "19_19") (pintype "passive"))
    )
    (net (code "180") (name "/VIBE_ON") (class "Default")
      (node (ref "U11F") (pin "G13") (pinfunction "IO_0_15_G13") (pintype "bidirectional"))
    )
    (net (code "181") (name "/V_AES") (class "Default")
      (node (ref "C69F") (pin "2") (pinfunction "2_2") (pintype "passive"))
      (node (ref "U11F") (pin "B8") (pinfunction "VCCBATT_0_B8") (pintype "power_in"))
      (node (ref "U19F") (pin "1") (pinfunction "OUT_1") (pintype "power_in"))
    )
    (net (code "182") (name "/WIFI_LPCLK") (class "Default")
      (node (ref "U11F") (pin "N15") (pinfunction "IO_L12P_T1_MRCC_14_N15") (pintype "bidirectional"))
    )
    (net (code "183") (name "/XADC_VDD") (class "Default")
      (node (ref "C10F") (pin "1") (pinfunction "1_1") (pintype "passive"))
      (node (ref "C13F") (pin "1") (pinfunction "1_1") (pintype "passive"))
      (node (ref "L10F") (pin "2") (pinfunction "2_2") (pintype "passive"))
      (node (ref "U10F") (pin "1") (pinfunction "IN_1") (pintype "power_in"))
      (node (ref "U11F") (pin "H10") (pinfunction "VCCADC_0_H10") (pintype "power_in"))
    )
    (net (code "184") (name "/XADC_VREF") (class "Default")
      (node (ref "C11F") (pin "1") (pinfunction "1_1") (pintype "passive"))
      (node (ref "C12F") (pin "1") (pinfunction "1_1") (pintype "passive"))
      (node (ref "U10F") (pin "2") (pinfunction "OUT_2") (pintype "power_in"))
      (node (ref "U11F") (pin "K10") (pinfunction "VREFP_0_K10") (pintype "power_in"))
    )
    (net (code "185") (name "GND") (class "Default")
      (node (ref "C14F") (pin "2") (pinfunction "2_2") (pintype "passive"))
      (node (ref "C15F") (pin "2") (pinfunction "2_2") (pintype "passive"))
      (node (ref "C16F") (pin "2") (pinfunction "2_2") (pintype "passive"))
      (node (ref "C17F") (pin "2") (pinfunction "2_2") (pintype "passive"))
      (node (ref "C18F") (pin "2") (pinfunction "2_2") (pintype "passive"))
      (node (ref "C19F") (pin "2") (pinfunction "2_2") (pintype "passive"))
      (node (ref "C20F") (pin "2") (pinfunction "2_2") (pintype "passive"))
      (node (ref "C21F") (pin "2") (pinfunction "2_2") (pintype "passive"))
      (node (ref "C22F") (pin "1") (pinfunction "1_1") (pintype "passive"))
      (node (ref "C23F") (pin "2") (pinfunction "2_2") (pintype "passive"))
      (node (ref "C24F") (pin "2") (pinfunction "2_2") (pintype "passive"))
      (node (ref "C25F") (pin "2") (pinfunction "2_2") (pintype "passive"))
      (node (ref "C26F") (pin "2") (pinfunction "2_2") (pintype "passive"))
      (node (ref "C27F") (pin "1") (pinfunction "1_1") (pintype "passive"))
      (node (ref "C28F") (pin "2") (pinfunction "2_2") (pintype "passive"))
      (node (ref "C29F") (pin "2") (pinfunction "2_2") (pintype "passive"))
      (node (ref "C30F") (pin "1") (pinfunction "1_1") (pintype "passive"))
      (node (ref "C31F") (pin "2") (pinfunction "2_2") (pintype "passive"))
      (node (ref "C32F") (pin "2") (pinfunction "2_2") (pintype "passive"))
      (node (ref "C33F") (pin "2") (pinfunction "2_2") (pintype "passive"))
      (node (ref "C34F") (pin "2") (pinfunction "2_2") (pintype "passive"))
      (node (ref "C35F") (pin "2") (pinfunction "2_2") (pintype "passive"))
      (node (ref "C36F") (pin "2") (pinfunction "2_2") (pintype "passive"))
      (node (ref "C37F") (pin "1") (pinfunction "1_1") (pintype "passive"))
      (node (ref "C38F") (pin "2") (pinfunction "2_2") (pintype "passive"))
      (node (ref "C39F") (pin "2") (pinfunction "2_2") (pintype "passive"))
      (node (ref "C40F") (pin "1") (pinfunction "1_1") (pintype "passive"))
      (node (ref "C41F") (pin "2") (pinfunction "2_2") (pintype "passive"))
      (node (ref "C42F") (pin "2") (pinfunction "2_2") (pintype "passive"))
      (node (ref "C43F") (pin "2") (pinfunction "2_2") (pintype "passive"))
      (node (ref "C44F") (pin "2") (pinfunction "2_2") (pintype "passive"))
      (node (ref "C45F") (pin "2") (pinfunction "2_2") (pintype "passive"))
      (node (ref "C46F") (pin "2") (pinfunction "2_2") (pintype "passive"))
      (node (ref "C47F") (pin "1") (pinfunction "1_1") (pintype "passive"))
      (node (ref "C48F") (pin "2") (pinfunction "2_2") (pintype "passive"))
      (node (ref "C49F") (pin "2") (pinfunction "2_2") (pintype "passive"))
      (node (ref "C50F") (pin "2") (pinfunction "2_2") (pintype "passive"))
      (node (ref "C51F") (pin "2") (pinfunction "2_2") (pintype "passive"))
      (node (ref "C52F") (pin "1") (pinfunction "1_1") (pintype "passive"))
      (node (ref "C53F") (pin "2") (pinfunction "2_2") (pintype "passive"))
      (node (ref "C54F") (pin "2") (pinfunction "2_2") (pintype "passive"))
      (node (ref "C55F") (pin "1") (pinfunction "1_1") (pintype "passive"))
      (node (ref "C56F") (pin "2") (pinfunction "2_2") (pintype "passive"))
      (node (ref "C57F") (pin "2") (pinfunction "2_2") (pintype "passive"))
      (node (ref "C58F") (pin "2") (pinfunction "2_2") (pintype "passive"))
      (node (ref "C59F") (pin "2") (pinfunction "2_2") (pintype "passive"))
      (node (ref "C60F") (pin "2") (pinfunction "2_2") (pintype "passive"))
      (node (ref "C61F") (pin "2") (pinfunction "2_2") (pintype "passive"))
      (node (ref "C62F") (pin "2") (pinfunction "2_2") (pintype "passive"))
      (node (ref "C63F") (pin "2") (pinfunction "2_2") (pintype "passive"))
      (node (ref "C64F") (pin "2") (pinfunction "2_2") (pintype "passive"))
      (node (ref "C65F") (pin "2") (pinfunction "2_2") (pintype "passive"))
      (node (ref "C66F") (pin "2") (pinfunction "2_2") (pintype "passive"))
      (node (ref "C67F") (pin "1") (pinfunction "1_1") (pintype "passive"))
      (node (ref "C68F") (pin "2") (pinfunction "2_2") (pintype "passive"))
      (node (ref "C69F") (pin "1") (pinfunction "1_1") (pintype "passive"))
      (node (ref "C70F") (pin "1") (pinfunction "1_1") (pintype "passive"))
      (node (ref "C71F") (pin "1") (pinfunction "1_1") (pintype "passive"))
      (node (ref "C72F") (pin "2") (pinfunction "2_2") (pintype "passive"))
      (node (ref "C73F") (pin "2") (pinfunction "2_2") (pintype "passive"))
      (node (ref "C74F") (pin "2") (pinfunction "2_2") (pintype "passive"))
      (node (ref "C75F") (pin "2") (pinfunction "2_2") (pintype "passive"))
      (node (ref "L11F") (pin "1") (pinfunction "1_1") (pintype "passive"))
      (node (ref "P11F") (pin "1") (pinfunction "1_1") (pintype "passive"))
      (node (ref "P11F") (pin "15") (pinfunction "15_15") (pintype "passive"))
      (node (ref "P11F") (pin "2") (pinfunction "2_2") (pintype "passive"))
      (node (ref "P11F") (pin "21") (pinfunction "21_21") (pintype "passive"))
      (node (ref "P11F") (pin "3") (pinfunction "3_3") (pintype "passive"))
      (node (ref "P11F") (pin "8") (pinfunction "8_8") (pintype "passive"))
      (node (ref "P12F") (pin "1") (pinfunction "1_1") (pintype "passive"))
      (node (ref "P12F") (pin "11") (pinfunction "11_11") (pintype "passive"))
      (node (ref "P12F") (pin "16") (pinfunction "16_16") (pintype "passive"))
      (node (ref "P12F") (pin "17") (pinfunction "17_17") (pintype "passive"))
      (node (ref "P12F") (pin "24") (pinfunction "24_24") (pintype "passive"))
      (node (ref "Q11F") (pin "2") (pinfunction "S_2") (pintype "passive"))
      (node (ref "Q12F") (pin "2") (pinfunction "S_2") (pintype "passive"))
      (node (ref "Q13F") (pin "2") (pinfunction "S_2") (pintype "passive"))
      (node (ref "Q14F") (pin "2") (pinfunction "S_2") (pintype "passive"))
      (node (ref "Q15F") (pin "2") (pinfunction "S_2") (pintype "passive"))
      (node (ref "Q17F") (pin "2") (pinfunction "S_2") (pintype "passive"))
      (node (ref "Q18F") (pin "2") (pinfunction "S_2") (pintype "passive"))
      (node (ref "Q19F") (pin "2") (pinfunction "S_2") (pintype "passive"))
      (node (ref "Q20F") (pin "2") (pinfunction "S_2") (pintype "passive"))
      (node (ref "Q21F") (pin "2") (pinfunction "S_2") (pintype "passive"))
      (node (ref "Q22F") (pin "2") (pinfunction "S_2") (pintype "passive"))
      (node (ref "R11F") (pin "2") (pinfunction "2_2") (pintype "passive"))
      (node (ref "R14F") (pin "1") (pinfunction "1_1") (pintype "passive"))
      (node (ref "R17F") (pin "1") (pinfunction "1_1") (pintype "passive"))
      (node (ref "R18F") (pin "1") (pinfunction "1_1") (pintype "passive"))
      (node (ref "R23F") (pin "1") (pinfunction "1_1") (pintype "passive"))
      (node (ref "R27F") (pin "2") (pinfunction "2_2") (pintype "passive"))
      (node (ref "R28F") (pin "1") (pinfunction "1_1") (pintype "passive"))
      (node (ref "R33F") (pin "1") (pinfunction "1_1") (pintype "passive"))
      (node (ref "R35F") (pin "2") (pinfunction "2_2") (pintype "passive"))
      (node (ref "R41F") (pin "1") (pinfunction "1_1") (pintype "passive"))
      (node (ref "U11F") (pin "A1") (pinfunction "GND_A1") (pintype "power_in"))
      (node (ref "U11F") (pin "A12") (pinfunction "GND_A12") (pintype "power_in"))
      (node (ref "U11F") (pin "A18") (pinfunction "GND_A18") (pintype "power_in"))
      (node (ref "U11F") (pin "A2") (pinfunction "IO_L10N_T1_AD15N_35_A2") (pintype "bidirectional"))
      (node (ref "U11F") (pin "A7") (pinfunction "IO_L1N_T0_AD4N_35_A7") (pintype "bidirectional"))
      (node (ref "U11F") (pin "B3") (pinfunction "IO_L8N_T1_AD14N_35_B3") (pintype "bidirectional"))
      (node (ref "U11F") (pin "B4") (pinfunction "IO_L7N_T1_AD6N_35_B4") (pintype "bidirectional"))
      (node (ref "U11F") (pin "B5") (pinfunction "IO_L2N_T0_AD12N_35_B5") (pintype "bidirectional"))
      (node (ref "U11F") (pin "B9") (pinfunction "GND_B9") (pintype "power_in"))
      (node (ref "U11F") (pin "C16") (pinfunction "GND_C16") (pintype "power_in"))
      (node (ref "U11F") (pin "C6") (pinfunction "GND_C6") (pintype "power_in"))
      (node (ref "U11F") (pin "C7") (pinfunction "IO_L3N_T0_DQS_AD5N_35_C7") (pintype "bidirectional"))
      (node (ref "U11F") (pin "D13") (pinfunction "GND_D13") (pintype "power_in"))
      (node (ref "U11F") (pin "D3") (pinfunction "GND_D3") (pintype "power_in"))
      (node (ref "U11F") (pin "E10") (pinfunction "GND_E10") (pintype "power_in"))
      (node (ref "U11F") (pin "E17") (pinfunction "IO_L10N_T1_AD11N_15_E17") (pintype "bidirectional"))
      (node (ref "U11F") (pin "E8") (pinfunction "GND_E8") (pintype "power_in"))
      (node (ref "U11F") (pin "F11") (pinfunction "GND_F11") (pintype "power_in"))
      (node (ref "U11F") (pin "F17") (pinfunction "GND_F17") (pintype "power_in"))
      (node (ref "U11F") (pin "F7") (pinfunction "GND_F7") (pintype "power_in"))
      (node (ref "U11F") (pin "F9") (pinfunction "GND_F9") (pintype "power_in"))
      (node (ref "U11F") (pin "G10") (pinfunction "GND_G10") (pintype "power_in"))
      (node (ref "U11F") (pin "G12") (pinfunction "GND_G12") (pintype "power_in"))
      (node (ref "U11F") (pin "G14") (pinfunction "GND_G14") (pintype "power_in"))
      (node (ref "U11F") (pin "G4") (pinfunction "GND_G4") (pintype "power_in"))
      (node (ref "U11F") (pin "G8") (pinfunction "GND_G8") (pintype "power_in"))
      (node (ref "U11F") (pin "H1") (pinfunction "GND_H1") (pintype "power_in"))
      (node (ref "U11F") (pin "H11") (pinfunction "GND_H11") (pintype "power_in"))
      (node (ref "U11F") (pin "H7") (pinfunction "GND_H7") (pintype "power_in"))
      (node (ref "U11F") (pin "J12") (pinfunction "GND_J12") (pintype "power_in"))
      (node (ref "U11F") (pin "J18") (pinfunction "GND_J18") (pintype "power_in"))
      (node (ref "U11F") (pin "J8") (pinfunction "GND_J8") (pintype "power_in"))
      (node (ref "U11F") (pin "K11") (pinfunction "GND_K11") (pintype "power_in"))
      (node (ref "U11F") (pin "K15") (pinfunction "GND_K15") (pintype "power_in"))
      (node (ref "U11F") (pin "K5") (pinfunction "GND_K5") (pintype "power_in"))
      (node (ref "U11F") (pin "K7") (pinfunction "GND_K7") (pintype "power_in"))
      (node (ref "U11F") (pin "L12") (pinfunction "GND_L12") (pintype "power_in"))
      (node (ref "U11F") (pin "L2") (pinfunction "GND_L2") (pintype "power_in"))
      (node (ref "U11F") (pin "L8") (pinfunction "GND_L8") (pintype "power_in"))
      (node (ref "U11F") (pin "M11") (pinfunction "GND_M11") (pintype "power_in"))
      (node (ref "U11F") (pin "M7") (pinfunction "GND_M7") (pintype "power_in"))
      (node (ref "U11F") (pin "M9") (pinfunction "GND_M9") (pintype "power_in"))
      (node (ref "U11F") (pin "N10") (pinfunction "GND_N10") (pintype "power_in"))
      (node (ref "U11F") (pin "N12") (pinfunction "GND_N12") (pintype "power_in"))
      (node (ref "U11F") (pin "N16") (pinfunction "GND_N16") (pintype "power_in"))
      (node (ref "U11F") (pin "N6") (pinfunction "GND_N6") (pintype "power_in"))
      (node (ref "U11F") (pin "N8") (pinfunction "GND_N8") (pintype "power_in"))
      (node (ref "U11F") (pin "P11") (pinfunction "GND_P11") (pintype "power_in"))
      (node (ref "U11F") (pin "P3") (pinfunction "GND_P3") (pintype "power_in"))
      (node (ref "U11F") (pin "P9") (pinfunction "GND_P9") (pintype "power_in"))
      (node (ref "U11F") (pin "R10") (pinfunction "GND_R10") (pintype "power_in"))
      (node (ref "U11F") (pin "T17") (pinfunction "GND_T17") (pintype "power_in"))
      (node (ref "U11F") (pin "T7") (pinfunction "GND_T7") (pintype "power_in"))
      (node (ref "U11F") (pin "U14") (pinfunction "GND_U14") (pintype "power_in"))
      (node (ref "U11F") (pin "U4") (pinfunction "GND_U4") (pintype "power_in"))
      (node (ref "U11F") (pin "V1") (pinfunction "GND_V1") (pintype "power_in"))
      (node (ref "U11F") (pin "V11") (pinfunction "GND_V11") (pintype "power_in"))
      (node (ref "U11F") (pin "V18") (pinfunction "GND_V18") (pintype "power_in"))
      (node (ref "U11F") (pin "V9") (pinfunction "CFGBVS_0_V9") (pintype "input"))
      (node (ref "U12F") (pin "A1") (pinfunction "GND_A1") (pintype "power_in"))
      (node (ref "U13F") (pin "A1") (pinfunction "GND_A1") (pintype "power_in"))
      (node (ref "U13F") (pin "C1") (pinfunction "VSEL/MODE_C1") (pintype "input"))
      (node (ref "U14F") (pin "5") (pinfunction "GND_5") (pintype "power_in"))
      (node (ref "U15F") (pin "1") (pinfunction "ST_1") (pintype "input"))
      (node (ref "U15F") (pin "4") (pinfunction "GND_4") (pintype "power_in"))
      (node (ref "U16F") (pin "C1") (pinfunction "GND_C1") (pintype "power_in"))
      (node (ref "U17F") (pin "C1") (pinfunction "GND_C1") (pintype "power_in"))
      (node (ref "U18F") (pin "7") (pinfunction "VSS_7") (pintype "power_in"))
      (node (ref "U19F") (pin "2") (pinfunction "GND_2") (pintype "power_in"))
      (node (ref "U19F") (pin "EP") (pinfunction "EP_EP") (pintype "power_in"))
    )
    (net (code "186") (name "Net-(Q10F-G)") (class "Default")
      (node (ref "Q10F") (pin "1") (pinfunction "G_1") (pintype "passive"))
      (node (ref "Q16F") (pin "3") (pinfunction "D_3") (pintype "passive"))
      (node (ref "R10F") (pin "1") (pinfunction "1_1") (pintype "passive"))
      (node (ref "R36F") (pin "2") (pinfunction "2_2") (pintype "passive"))
    )
    (net (code "187") (name "Net-(Q14F-D)") (class "Default")
      (node (ref "Q14F") (pin "3") (pinfunction "D_3") (pintype "passive"))
      (node (ref "R20F") (pin "1") (pinfunction "1_1") (pintype "passive"))
    )
    (net (code "188") (name "Net-(Q22F-D)") (class "Default")
      (node (ref "Q22F") (pin "3") (pinfunction "D_3") (pintype "passive"))
      (node (ref "R40F") (pin "2") (pinfunction "2_2") (pintype "passive"))
    )
    (net (code "189") (name "Net-(U11FA-DONE_0)") (class "Default")
      (node (ref "R13F") (pin "1") (pinfunction "1_1") (pintype "passive"))
      (node (ref "U11F") (pin "V8") (pinfunction "DONE_0_V8") (pintype "open_collector"))
    )
    (net (code "190") (name "Net-(U11FA-M0_0)") (class "Default")
      (node (ref "R19F") (pin "2") (pinfunction "2_2") (pintype "passive"))
      (node (ref "U11F") (pin "T10") (pinfunction "M0_0_T10") (pintype "input"))
    )
    (net (code "191") (name "Net-(U11FA-M1_0)") (class "Default")
      (node (ref "R18F") (pin "2") (pinfunction "2_2") (pintype "passive"))
      (node (ref "U11F") (pin "U10") (pinfunction "M1_0_U10") (pintype "input"))
    )
    (net (code "192") (name "Net-(U11FA-M2_0)") (class "Default")
      (node (ref "R17F") (pin "2") (pinfunction "2_2") (pintype "passive"))
      (node (ref "U11F") (pin "U9") (pinfunction "M2_0_U9") (pintype "input"))
    )
    (net (code "193") (name "Net-(U11FB-IO_L3P_T0_DQS_PUDC_B_14)") (class "Default")
      (node (ref "R22F") (pin "1") (pinfunction "1_1") (pintype "passive"))
      (node (ref "U11F") (pin "L15") (pinfunction "IO_L3P_T0_DQS_PUDC_B_14_L15") (pintype "bidirectional"))
    )
    (net (code "194") (name "Net-(U12F-EN)") (class "Default")
      (node (ref "R12F") (pin "1") (pinfunction "1_1") (pintype "passive"))
      (node (ref "U12F") (pin "C2") (pinfunction "EN_C2") (pintype "input"))
    )
    (net (code "195") (name "Net-(U12F-VSEL{slash}MODE)") (class "Default")
      (node (ref "R11F") (pin "1") (pinfunction "1_1") (pintype "passive"))
      (node (ref "U12F") (pin "C1") (pinfunction "VSEL/MODE_C1") (pintype "input"))
    )
    (net (code "196") (name "P0.95V_T") (class "Default")
      (node (ref "C16F") (pin "1") (pinfunction "1_1") (pintype "passive"))
      (node (ref "C19F") (pin "1") (pinfunction "1_1") (pintype "passive"))
      (node (ref "C20F") (pin "1") (pinfunction "1_1") (pintype "passive"))
      (node (ref "C21F") (pin "1") (pinfunction "1_1") (pintype "passive"))
      (node (ref "C22F") (pin "2") (pinfunction "2_2") (pintype "passive"))
      (node (ref "C23F") (pin "1") (pinfunction "1_1") (pintype "passive"))
      (node (ref "C24F") (pin "1") (pinfunction "1_1") (pintype "passive"))
      (node (ref "C25F") (pin "1") (pinfunction "1_1") (pintype "passive"))
      (node (ref "C26F") (pin "1") (pinfunction "1_1") (pintype "passive"))
      (node (ref "C27F") (pin "2") (pinfunction "2_2") (pintype "passive"))
      (node (ref "C28F") (pin "1") (pinfunction "1_1") (pintype "passive"))
      (node (ref "C60F") (pin "1") (pinfunction "1_1") (pintype "passive"))
      (node (ref "C61F") (pin "1") (pinfunction "1_1") (pintype "passive"))
      (node (ref "L12F") (pin "2") (pinfunction "2_2") (pintype "passive"))
      (node (ref "R16F") (pin "1") (pinfunction "1_1") (pintype "passive"))
      (node (ref "R20F") (pin "2") (pinfunction "2_2") (pintype "passive"))
      (node (ref "U11F") (pin "E11") (pinfunction "VCCINT_E11") (pintype "power_in"))
      (node (ref "U11F") (pin "E7") (pinfunction "VCCINT_E7") (pintype "power_in"))
      (node (ref "U11F") (pin "E9") (pinfunction "VCCINT_E9") (pintype "power_in"))
      (node (ref "U11F") (pin "F10") (pinfunction "VCCINT_F10") (pintype "power_in"))
      (node (ref "U11F") (pin "F8") (pinfunction "VCCINT_F8") (pintype "power_in"))
      (node (ref "U11F") (pin "G11") (pinfunction "VCCINT_G11") (pintype "power_in"))
      (node (ref "U11F") (pin "G7") (pinfunction "VCCINT_G7") (pintype "power_in"))
      (node (ref "U11F") (pin "G9") (pinfunction "VCCINT_G9") (pintype "power_in"))
      (node (ref "U11F") (pin "H8") (pinfunction "VCCINT_H8") (pintype "power_in"))
      (node (ref "U11F") (pin "J11") (pinfunction "VCCINT_J11") (pintype "power_in"))
      (node (ref "U11F") (pin "J7") (pinfunction "VCCINT_J7") (pintype "power_in"))
      (node (ref "U11F") (pin "K8") (pinfunction "VCCINT_K8") (pintype "power_in"))
      (node (ref "U11F") (pin "L11") (pinfunction "VCCINT_L11") (pintype "power_in"))
      (node (ref "U11F") (pin "L7") (pinfunction "VCCBRAM_L7") (pintype "power_in"))
      (node (ref "U11F") (pin "M10") (pinfunction "VCCINT_M10") (pintype "power_in"))
      (node (ref "U11F") (pin "M8") (pinfunction "VCCINT_M8") (pintype "power_in"))
      (node (ref "U11F") (pin "N11") (pinfunction "VCCINT_N11") (pintype "power_in"))
      (node (ref "U11F") (pin "N7") (pinfunction "VCCBRAM_N7") (pintype "power_in"))
      (node (ref "U11F") (pin "N9") (pinfunction "VCCINT_N9") (pintype "power_in"))
      (node (ref "U11F") (pin "P10") (pinfunction "VCCINT_P10") (pintype "power_in"))
      (node (ref "U11F") (pin "P8") (pinfunction "VCCINT_P8") (pintype "power_in"))
      (node (ref "U12F") (pin "A2") (pinfunction "VOS_A2") (pintype "input"))
    )
    (net (code "197") (name "P1.8V") (class "Default")
      (node (ref "C37F") (pin "2") (pinfunction "2_2") (pintype "passive"))
      (node (ref "P11F") (pin "16") (pinfunction "16_16") (pintype "passive"))
      (node (ref "P12F") (pin "9") (pinfunction "9_9") (pintype "passive"))
    )
    (net (code "198") (name "P1.8V_SBY") (class "Default")
      (node (ref "D11F") (pin "1") (pinfunction "A_1") (pintype "passive"))
      (node (ref "R38F") (pin "1") (pinfunction "1_1") (pintype "passive"))
      (node (ref "R39F") (pin "2") (pinfunction "2_2") (pintype "passive"))
      (node (ref "U16F") (pin "A2") (pinfunction "VCC_A2") (pintype "power_in"))
      (node (ref "U17F") (pin "A2") (pinfunction "VCC_A2") (pintype "power_in"))
    )
    (net (code "199") (name "P1.8V_T") (class "Default")
      (node (ref "C18F") (pin "1") (pinfunction "1_1") (pintype "passive"))
      (node (ref "C29F") (pin "1") (pinfunction "1_1") (pintype "passive"))
      (node (ref "C30F") (pin "2") (pinfunction "2_2") (pintype "passive"))
      (node (ref "C31F") (pin "1") (pinfunction "1_1") (pintype "passive"))
      (node (ref "C32F") (pin "1") (pinfunction "1_1") (pintype "passive"))
      (node (ref "C35F") (pin "1") (pinfunction "1_1") (pintype "passive"))
      (node (ref "C38F") (pin "1") (pinfunction "1_1") (pintype "passive"))
      (node (ref "C39F") (pin "1") (pinfunction "1_1") (pintype "passive"))
      (node (ref "C40F") (pin "2") (pinfunction "2_2") (pintype "passive"))
      (node (ref "C41F") (pin "1") (pinfunction "1_1") (pintype "passive"))
      (node (ref "C42F") (pin "1") (pinfunction "1_1") (pintype "passive"))
      (node (ref "C43F") (pin "1") (pinfunction "1_1") (pintype "passive"))
      (node (ref "C44F") (pin "1") (pinfunction "1_1") (pintype "passive"))
      (node (ref "C52F") (pin "2") (pinfunction "2_2") (pintype "passive"))
      (node (ref "C53F") (pin "1") (pinfunction "1_1") (pintype "passive"))
      (node (ref "C54F") (pin "1") (pinfunction "1_1") (pintype "passive"))
      (node (ref "C55F") (pin "2") (pinfunction "2_2") (pintype "passive"))
      (node (ref "C56F") (pin "1") (pinfunction "1_1") (pintype "passive"))
      (node (ref "C57F") (pin "1") (pinfunction "1_1") (pintype "passive"))
      (node (ref "C58F") (pin "1") (pinfunction "1_1") (pintype "passive"))
      (node (ref "C59F") (pin "1") (pinfunction "1_1") (pintype "passive"))
      (node (ref "C62F") (pin "1") (pinfunction "1_1") (pintype "passive"))
      (node (ref "C67F") (pin "2") (pinfunction "2_2") (pintype "passive"))
      (node (ref "C68F") (pin "1") (pinfunction "1_1") (pintype "passive"))
      (node (ref "L10F") (pin "1") (pinfunction "1_1") (pintype "passive"))
      (node (ref "L13F") (pin "2") (pinfunction "2_2") (pintype "passive"))
      (node (ref "P12F") (pin "18") (pinfunction "18_18") (pintype "passive"))
      (node (ref "R13F") (pin "2") (pinfunction "2_2") (pintype "passive"))
      (node (ref "R15F") (pin "2") (pinfunction "2_2") (pintype "passive"))
      (node (ref "R19F") (pin "1") (pinfunction "1_1") (pintype "passive"))
      (node (ref "R21F") (pin "2") (pinfunction "2_2") (pintype "passive"))
      (node (ref "R22F") (pin "2") (pinfunction "2_2") (pintype "passive"))
      (node (ref "R24F") (pin "2") (pinfunction "2_2") (pintype "passive"))
      (node (ref "R30F") (pin "1") (pinfunction "1_1") (pintype "passive"))
      (node (ref "R31F") (pin "1") (pinfunction "1_1") (pintype "passive"))
      (node (ref "R34F") (pin "1") (pinfunction "1_1") (pintype "passive"))
      (node (ref "U11F") (pin "B10") (pinfunction "VCCO_16_B10") (pintype "power_in"))
      (node (ref "U11F") (pin "B12") (pinfunction "VCCO_16_B12") (pintype "power_in"))
      (node (ref "U11F") (pin "D8") (pinfunction "VCCO_0_D8") (pintype "power_in"))
      (node (ref "U11F") (pin "F12") (pinfunction "VCCAUX_F12") (pintype "power_in"))
      (node (ref "U11F") (pin "H12") (pinfunction "VCCAUX_H12") (pintype "power_in"))
      (node (ref "U11F") (pin "K12") (pinfunction "VCCAUX_K12") (pintype "power_in"))
      (node (ref "U11F") (pin "L3") (pinfunction "VCCO_34_L3") (pintype "power_in"))
      (node (ref "U11F") (pin "M12") (pinfunction "VCCAUX_M12") (pintype "power_in"))
      (node (ref "U11F") (pin "N17") (pinfunction "VCCO_14_N17") (pintype "power_in"))
      (node (ref "U11F") (pin "P12") (pinfunction "VCCAUX_P12") (pintype "power_in"))
      (node (ref "U11F") (pin "P4") (pinfunction "VCCO_34_P4") (pintype "power_in"))
      (node (ref "U11F") (pin "T16") (pinfunction "VCCO_14_T16") (pintype "power_in"))
      (node (ref "U11F") (pin "U13") (pinfunction "VCCO_14_U13") (pintype "power_in"))
      (node (ref "U11F") (pin "U5") (pinfunction "VCCO_34_U5") (pintype "power_in"))
      (node (ref "U11F") (pin "V10") (pinfunction "VCCO_0_V10") (pintype "power_in"))
      (node (ref "U13F") (pin "A2") (pinfunction "VOS_A2") (pintype "input"))
      (node (ref "U15F") (pin "3") (pinfunction "VDD_3") (pintype "power_in"))
    )
    (net (code "200") (name "P3.3V") (class "Default")
      (node (ref "P11F") (pin "20") (pinfunction "20_20") (pintype "passive"))
    )
    (net (code "201") (name "P3.3V_A") (class "Default")
      (node (ref "C33F") (pin "1") (pinfunction "1_1") (pintype "passive"))
      (node (ref "C45F") (pin "1") (pinfunction "1_1") (pintype "passive"))
      (node (ref "C46F") (pin "1") (pinfunction "1_1") (pintype "passive"))
      (node (ref "C47F") (pin "2") (pinfunction "2_2") (pintype "passive"))
      (node (ref "C48F") (pin "1") (pinfunction "1_1") (pintype "passive"))
      (node (ref "C49F") (pin "1") (pinfunction "1_1") (pintype "passive"))
      (node (ref "C50F") (pin "1") (pinfunction "1_1") (pintype "passive"))
      (node (ref "C51F") (pin "1") (pinfunction "1_1") (pintype "passive"))
      (node (ref "C71F") (pin "2") (pinfunction "2_2") (pintype "passive"))
      (node (ref "C72F") (pin "1") (pinfunction "1_1") (pintype "passive"))
      (node (ref "C73F") (pin "1") (pinfunction "1_1") (pintype "passive"))
      (node (ref "C74F") (pin "1") (pinfunction "1_1") (pintype "passive"))
      (node (ref "R25F") (pin "2") (pinfunction "2_2") (pintype "passive"))
      (node (ref "R26F") (pin "2") (pinfunction "2_2") (pintype "passive"))
      (node (ref "R32F") (pin "2") (pinfunction "2_2") (pintype "passive"))
      (node (ref "U11F") (pin "B6") (pinfunction "VCCO_35_B6") (pintype "power_in"))
      (node (ref "U11F") (pin "C15") (pinfunction "VCCO_15_C15") (pintype "power_in"))
      (node (ref "U11F") (pin "D4") (pinfunction "VCCO_35_D4") (pintype "power_in"))
      (node (ref "U11F") (pin "F16") (pinfunction "VCCO_15_F16") (pintype "power_in"))
      (node (ref "U11F") (pin "G3") (pinfunction "VCCO_35_G3") (pintype "power_in"))
      (node (ref "U11F") (pin "J17") (pinfunction "VCCO_15_J17") (pintype "power_in"))
      (node (ref "U14F") (pin "2") (pinfunction "SUB_2") (pintype "power_in"))
      (node (ref "U14F") (pin "4") (pinfunction "VDD_4") (pintype "power_in"))
    )
    (net (code "202") (name "PACK_P") (class "Default")
      (node (ref "P11F") (pin "4") (pinfunction "4_4") (pintype "passive"))
      (node (ref "P11F") (pin "5") (pinfunction "5_5") (pintype "passive"))
      (node (ref "P11F") (pin "6") (pinfunction "6_6") (pintype "passive"))
    )
    (net (code "203") (name "VBAT") (class "Default")
      (node (ref "C66F") (pin "1") (pinfunction "1_1") (pintype "passive"))
      (node (ref "C70F") (pin "2") (pinfunction "2_2") (pintype "passive"))
      (node (ref "R37F") (pin "2") (pinfunction "2_2") (pintype "passive"))
      (node (ref "U18F") (pin "8") (pinfunction "VBACKUP_8") (pintype "power_in"))
      (node (ref "U19F") (pin "4") (pinfunction "IN_4") (pintype "input"))
    )
    (net (code "204") (name "VBUS") (class "Default")
      (node (ref "Q12F") (pin "1") (pinfunction "G_1") (pintype "passive"))
    )
    (net (code "205") (name "VBUS_SWITCHED") (class "Default")
      (node (ref "C63F") (pin "1") (pinfunction "1_1") (pintype "passive"))
      (node (ref "P12F") (pin "12") (pinfunction "12_12") (pintype "passive"))
      (node (ref "P12F") (pin "13") (pinfunction "13_13") (pintype "passive"))
      (node (ref "P12F") (pin "14") (pinfunction "14_14") (pintype "passive"))
    )
    (net (code "206") (name "VSYS_RAW") (class "Default")
      (node (ref "C36F") (pin "1") (pinfunction "1_1") (pintype "passive"))
      (node (ref "J10F") (pin "1") (pinfunction "1_1") (pintype "passive"))
      (node (ref "Q10F") (pin "4") (pinfunction "S_4") (pintype "passive"))
      (node (ref "R10F") (pin "2") (pinfunction "2_2") (pintype "passive"))
    )
    (net (code "207") (name "VSYS_T") (class "Default")
      (node (ref "C14F") (pin "1") (pinfunction "1_1") (pintype "passive"))
      (node (ref "C15F") (pin "1") (pinfunction "1_1") (pintype "passive"))
      (node (ref "C17F") (pin "1") (pinfunction "1_1") (pintype "passive"))
      (node (ref "J11F") (pin "1") (pinfunction "1_1") (pintype "passive"))
      (node (ref "J12F") (pin "1") (pinfunction "1_1") (pintype "passive"))
      (node (ref "Q10F") (pin "2") (pinfunction "D_2") (pintype "passive"))
      (node (ref "Q10F") (pin "3") (pinfunction "D_3") (pintype "passive"))
      (node (ref "R12F") (pin "2") (pinfunction "2_2") (pintype "passive"))
      (node (ref "U12F") (pin "B1") (pinfunction "VIN_B1") (pintype "power_in"))
      (node (ref "U13F") (pin "B1") (pinfunction "VIN_B1") (pintype "power_in"))
    )
    (net (code "208") (name "VSYS_U") (class "Default")
      (node (ref "P11F") (pin "9") (pinfunction "9_9") (pintype "passive"))
    )
    (net (code "209") (name "XADC_GND") (class "Default")
      (node (ref "C10F") (pin "2") (pinfunction "2_2") (pintype "passive"))
      (node (ref "C11F") (pin "2") (pinfunction "2_2") (pintype "passive"))
      (node (ref "C12F") (pin "2") (pinfunction "2_2") (pintype "passive"))
      (node (ref "C13F") (pin "2") (pinfunction "2_2") (pintype "passive"))
      (node (ref "L11F") (pin "2") (pinfunction "2_2") (pintype "passive"))
      (node (ref "U10F") (pin "3") (pinfunction "GND_3") (pintype "power_in"))
      (node (ref "U11F") (pin "H9") (pinfunction "GNDADC_0_H9") (pintype "power_in"))
      (node (ref "U11F") (pin "J9") (pinfunction "VREFN_0_J9") (pintype "power_in"))
      (node (ref "U11F") (pin "L10") (pinfunction "DXP_0_L10") (pintype "passive"))
      (node (ref "U11F") (pin "L9") (pinfunction "DXN_0_L9") (pintype "passive"))
    )
    (net (code "210") (name "unconnected-(P12F-Pad10)") (class "Default")
      (node (ref "P12F") (pin "10") (pinfunction "10_10") (pintype "passive"))
    )
    (net (code "211") (name "unconnected-(P12F-Pad15)") (class "Default")
      (node (ref "P12F") (pin "15") (pinfunction "15_15") (pintype "passive"))
    )
    (net (code "212") (name "unconnected-(U11FB-IO_25_14-PadR12)") (class "Default")
      (node (ref "U11F") (pin "R12") (pinfunction "IO_25_14_R12") (pintype "bidirectional"))
    )
    (net (code "213") (name "unconnected-(U11FB-IO_L6N_T0_D08_VREF_14-PadN13)") (class "Default")
      (node (ref "U11F") (pin "N13") (pinfunction "IO_L6N_T0_D08_VREF_14_N13") (pintype "bidirectional"))
    )
    (net (code "214") (name "unconnected-(U11FB-IO_L19P_T3_D26_14-PadP13)") (class "Default")
      (node (ref "U11F") (pin "P13") (pinfunction "IO_L19P_T3_D26_14_P13") (pintype "bidirectional"))
    )
    (net (code "215") (name "unconnected-(U11FB-IO_L22P_T3_D21_14-PadT12)") (class "Default")
      (node (ref "U11F") (pin "T12") (pinfunction "IO_L22P_T3_D21_14_T12") (pintype "bidirectional"))
    )
    (net (code "216") (name "unconnected-(U11FB-IO_L23N_T3_D18_14-PadT11)") (class "Default")
      (node (ref "U11F") (pin "T11") (pinfunction "IO_L23N_T3_D18_14_T11") (pintype "bidirectional"))
    )
    (net (code "217") (name "unconnected-(U11FB-IO_L23P_T3_D19_14-PadR11)") (class "Default")
      (node (ref "U11F") (pin "R11") (pinfunction "IO_L23P_T3_D19_14_R11") (pintype "bidirectional"))
    )
    (net (code "218") (name "unconnected-(U11FC-IO_25_15-PadK13)") (class "Default")
      (node (ref "U11F") (pin "K13") (pinfunction "IO_25_15_K13") (pintype "bidirectional"))
    )
    (net (code "219") (name "unconnected-(U11FC-IO_L14P_T2_SRCC_15-PadG16)") (class "Default")
      (node (ref "U11F") (pin "G16") (pinfunction "IO_L14P_T2_SRCC_15_G16") (pintype "bidirectional"))
    )
    (net (code "220") (name "unconnected-(U11FC-IO_L19N_T3_VREF_15-PadJ16)") (class "Default")
      (node (ref "U11F") (pin "J16") (pinfunction "IO_L19N_T3_VREF_15_J16") (pintype "bidirectional"))
    )
    (net (code "221") (name "unconnected-(U11FC-IO_L19P_T3_15-PadK16)") (class "Default")
      (node (ref "U11F") (pin "K16") (pinfunction "IO_L19P_T3_15_K16") (pintype "bidirectional"))
    )
    (net (code "222") (name "unconnected-(U11FC-IO_L20P_T3_15-PadH13)") (class "Default")
      (node (ref "U11F") (pin "H13") (pinfunction "IO_L20P_T3_15_H13") (pintype "bidirectional"))
    )
    (net (code "223") (name "unconnected-(U11FC-IO_L23N_T3_15-PadJ15)") (class "Default")
      (node (ref "U11F") (pin "J15") (pinfunction "IO_L23N_T3_15_J15") (pintype "bidirectional"))
    )
    (net (code "224") (name "unconnected-(U11FC-IO_L23P_T3_15-PadK14)") (class "Default")
      (node (ref "U11F") (pin "K14") (pinfunction "IO_L23P_T3_15_K14") (pintype "bidirectional"))
    )
    (net (code "225") (name "unconnected-(U11FC-IO_L24P_T3_RS1_15-PadJ13)") (class "Default")
      (node (ref "U11F") (pin "J13") (pinfunction "IO_L24P_T3_RS1_15_J13") (pintype "bidirectional+no_connect"))
    )
    (net (code "226") (name "unconnected-(U11FF-IO_0_35-PadF6)") (class "Default")
      (node (ref "U11F") (pin "F6") (pinfunction "IO_0_35_F6") (pintype "bidirectional"))
    )
    (net (code "227") (name "unconnected-(U11FF-IO_25_35-PadJ5)") (class "Default")
      (node (ref "U11F") (pin "J5") (pinfunction "IO_25_35_J5") (pintype "bidirectional"))
    )
    (net (code "228") (name "unconnected-(U11FF-IO_L4N_T0_35-PadA6)") (class "Default")
      (node (ref "U11F") (pin "A6") (pinfunction "IO_L4N_T0_35_A6") (pintype "bidirectional"))
    )
    (net (code "229") (name "unconnected-(U11FF-IO_L5N_T0_AD13N_35-PadD6)") (class "Default")
      (node (ref "U11F") (pin "D6") (pinfunction "IO_L5N_T0_AD13N_35_D6") (pintype "bidirectional"))
    )
    (net (code "230") (name "unconnected-(U11FF-IO_L5P_T0_AD13P_35-PadE6)") (class "Default")
      (node (ref "U11F") (pin "E6") (pinfunction "IO_L5P_T0_AD13P_35_E6") (pintype "bidirectional"))
    )
    (net (code "231") (name "unconnected-(U11FF-IO_L6N_T0_VREF_35-PadD5)") (class "Default")
      (node (ref "U11F") (pin "D5") (pinfunction "IO_L6N_T0_VREF_35_D5") (pintype "bidirectional"))
    )
    (net (code "232") (name "unconnected-(U11FF-IO_L6P_T0_35-PadE5)") (class "Default")
      (node (ref "U11F") (pin "E5") (pinfunction "IO_L6P_T0_35_E5") (pintype "bidirectional"))
    )
    (net (code "233") (name "unconnected-(U11FF-IO_L13N_T2_MRCC_35-PadE4)") (class "Default")
      (node (ref "U11F") (pin "E4") (pinfunction "IO_L13N_T2_MRCC_35_E4") (pintype "bidirectional"))
    )
    (net (code "234") (name "unconnected-(U11FF-IO_L13P_T2_MRCC_35-PadF4)") (class "Default")
      (node (ref "U11F") (pin "F4") (pinfunction "IO_L13P_T2_MRCC_35_F4") (pintype "bidirectional"))
    )
    (net (code "235") (name "unconnected-(U11FF-IO_L14P_T2_SRCC_35-PadE1)") (class "Default")
      (node (ref "U11F") (pin "E1") (pinfunction "IO_L14P_T2_SRCC_35_E1") (pintype "bidirectional"))
    )
    (net (code "236") (name "unconnected-(U11FF-IO_L15N_T2_DQS_35-PadE3)") (class "Default")
      (node (ref "U11F") (pin "E3") (pinfunction "IO_L15N_T2_DQS_35_E3") (pintype "bidirectional"))
    )
    (net (code "237") (name "unconnected-(U11FF-IO_L15P_T2_DQS_35-PadF3)") (class "Default")
      (node (ref "U11F") (pin "F3") (pinfunction "IO_L15P_T2_DQS_35_F3") (pintype "bidirectional"))
    )
    (net (code "238") (name "unconnected-(U11FF-IO_L16N_T2_35-PadD2)") (class "Default")
      (node (ref "U11F") (pin "D2") (pinfunction "IO_L16N_T2_35_D2") (pintype "bidirectional"))
    )
    (net (code "239") (name "unconnected-(U11FF-IO_L16P_T2_35-PadE2)") (class "Default")
      (node (ref "U11F") (pin "E2") (pinfunction "IO_L16P_T2_35_E2") (pintype "bidirectional"))
    )
    (net (code "240") (name "unconnected-(U11FF-IO_L17N_T2_35-PadF5)") (class "Default")
      (node (ref "U11F") (pin "F5") (pinfunction "IO_L17N_T2_35_F5") (pintype "bidirectional"))
    )
    (net (code "241") (name "unconnected-(U11FF-IO_L17P_T2_35-PadG5)") (class "Default")
      (node (ref "U11F") (pin "G5") (pinfunction "IO_L17P_T2_35_G5") (pintype "bidirectional"))
    )
    (net (code "242") (name "unconnected-(U11FF-IO_L18N_T2_35-PadF1)") (class "Default")
      (node (ref "U11F") (pin "F1") (pinfunction "IO_L18N_T2_35_F1") (pintype "bidirectional"))
    )
    (net (code "243") (name "unconnected-(U11FF-IO_L19N_T3_VREF_35-PadJ3)") (class "Default")
      (node (ref "U11F") (pin "J3") (pinfunction "IO_L19N_T3_VREF_35_J3") (pintype "bidirectional"))
    )
    (net (code "244") (name "unconnected-(U11FF-IO_L19P_T3_35-PadJ4)") (class "Default")
      (node (ref "U11F") (pin "J4") (pinfunction "IO_L19P_T3_35_J4") (pintype "bidirectional"))
    )
    (net (code "245") (name "unconnected-(U11FF-IO_L20N_T3_35-PadH2)") (class "Default")
      (node (ref "U11F") (pin "H2") (pinfunction "IO_L20N_T3_35_H2") (pintype "bidirectional"))
    )
    (net (code "246") (name "unconnected-(U11FF-IO_L20P_T3_35-PadH3)") (class "Default")
      (node (ref "U11F") (pin "H3") (pinfunction "IO_L20P_T3_35_H3") (pintype "bidirectional"))
    )
    (net (code "247") (name "unconnected-(U11FF-IO_L21N_T3_DQS_35-PadG1)") (class "Default")
      (node (ref "U11F") (pin "G1") (pinfunction "IO_L21N_T3_DQS_35_G1") (pintype "bidirectional"))
    )
    (net (code "248") (name "unconnected-(U11FF-IO_L22N_T3_35-PadH4)") (class "Default")
      (node (ref "U11F") (pin "H4") (pinfunction "IO_L22N_T3_35_H4") (pintype "bidirectional"))
    )
    (net (code "249") (name "unconnected-(U11FF-IO_L22P_T3_35-PadH5)") (class "Default")
      (node (ref "U11F") (pin "H5") (pinfunction "IO_L22P_T3_35_H5") (pintype "bidirectional"))
    )
    (net (code "250") (name "unconnected-(U11FF-IO_L23N_T3_35-PadJ1)") (class "Default")
      (node (ref "U11F") (pin "J1") (pinfunction "IO_L23N_T3_35_J1") (pintype "bidirectional"))
    )
    (net (code "251") (name "unconnected-(U11FF-IO_L23P_T3_35-PadJ2)") (class "Default")
      (node (ref "U11F") (pin "J2") (pinfunction "IO_L23P_T3_35_J2") (pintype "bidirectional"))
    )
    (net (code "252") (name "unconnected-(U11FF-IO_L24N_T3_35-PadG6)") (class "Default")
      (node (ref "U11F") (pin "G6") (pinfunction "IO_L24N_T3_35_G6") (pintype "bidirectional"))
    )
    (net (code "253") (name "unconnected-(U11FF-IO_L24P_T3_35-PadH6)") (class "Default")
      (node (ref "U11F") (pin "H6") (pinfunction "IO_L24P_T3_35_H6") (pintype "bidirectional"))
    )
    (net (code "254") (name "unconnected-(U11FG-IO_L6N_T0_VREF_16-PadD11)") (class "Default")
      (node (ref "U11F") (pin "D11") (pinfunction "IO_L6N_T0_VREF_16_D11") (pintype "bidirectional"))
    )
    (net (code "255") (name "unconnected-(U11FG-IO_L11N_T1_SRCC_16-PadC9)") (class "Default")
      (node (ref "U11F") (pin "C9") (pinfunction "IO_L11N_T1_SRCC_16_C9") (pintype "bidirectional"))
    )
    (net (code "256") (name "unconnected-(U11FG-IO_L11P_T1_SRCC_16-PadC10)") (class "Default")
      (node (ref "U11F") (pin "C10") (pinfunction "IO_L11P_T1_SRCC_16_C10") (pintype "bidirectional"))
    )
    (net (code "257") (name "unconnected-(U11FG-IO_L12N_T1_MRCC_16-PadA9)") (class "Default")
      (node (ref "U11F") (pin "A9") (pinfunction "IO_L12N_T1_MRCC_16_A9") (pintype "bidirectional"))
    )
    (net (code "258") (name "unconnected-(U11FG-IO_L12P_T1_MRCC_16-PadA10)") (class "Default")
      (node (ref "U11F") (pin "A10") (pinfunction "IO_L12P_T1_MRCC_16_A10") (pintype "bidirectional"))
    )
    (net (code "259") (name "unconnected-(U11FG-IO_L13N_T2_MRCC_16-PadC11)") (class "Default")
      (node (ref "U11F") (pin "C11") (pinfunction "IO_L13N_T2_MRCC_16_C11") (pintype "bidirectional"))
    )
    (net (code "260") (name "unconnected-(U11FG-IO_L14N_T2_SRCC_16-PadA11)") (class "Default")
      (node (ref "U11F") (pin "A11") (pinfunction "IO_L14N_T2_SRCC_16_A11") (pintype "bidirectional"))
    )
    (net (code "261") (name "unconnected-(U11FG-IO_L14P_T2_SRCC_16-PadB11)") (class "Default")
      (node (ref "U11F") (pin "B11") (pinfunction "IO_L14P_T2_SRCC_16_B11") (pintype "bidirectional"))
    )
    (net (code "262") (name "unconnected-(U11FG-IO_L19N_T3_VREF_16-PadD10)") (class "Default")
      (node (ref "U11F") (pin "D10") (pinfunction "IO_L19N_T3_VREF_16_D10") (pintype "bidirectional"))
    )
    (net (code "263") (name "unconnected-(U18F-CLKOUT-Pad5)") (class "Default")
      (node (ref "U18F") (pin "5") (pinfunction "CLKOUT_5") (pintype "open_collector"))
    )
  )
)
